# firefly_rp2354A.net
KiCad netlist of a schematic drawn in EasyEDA Pro
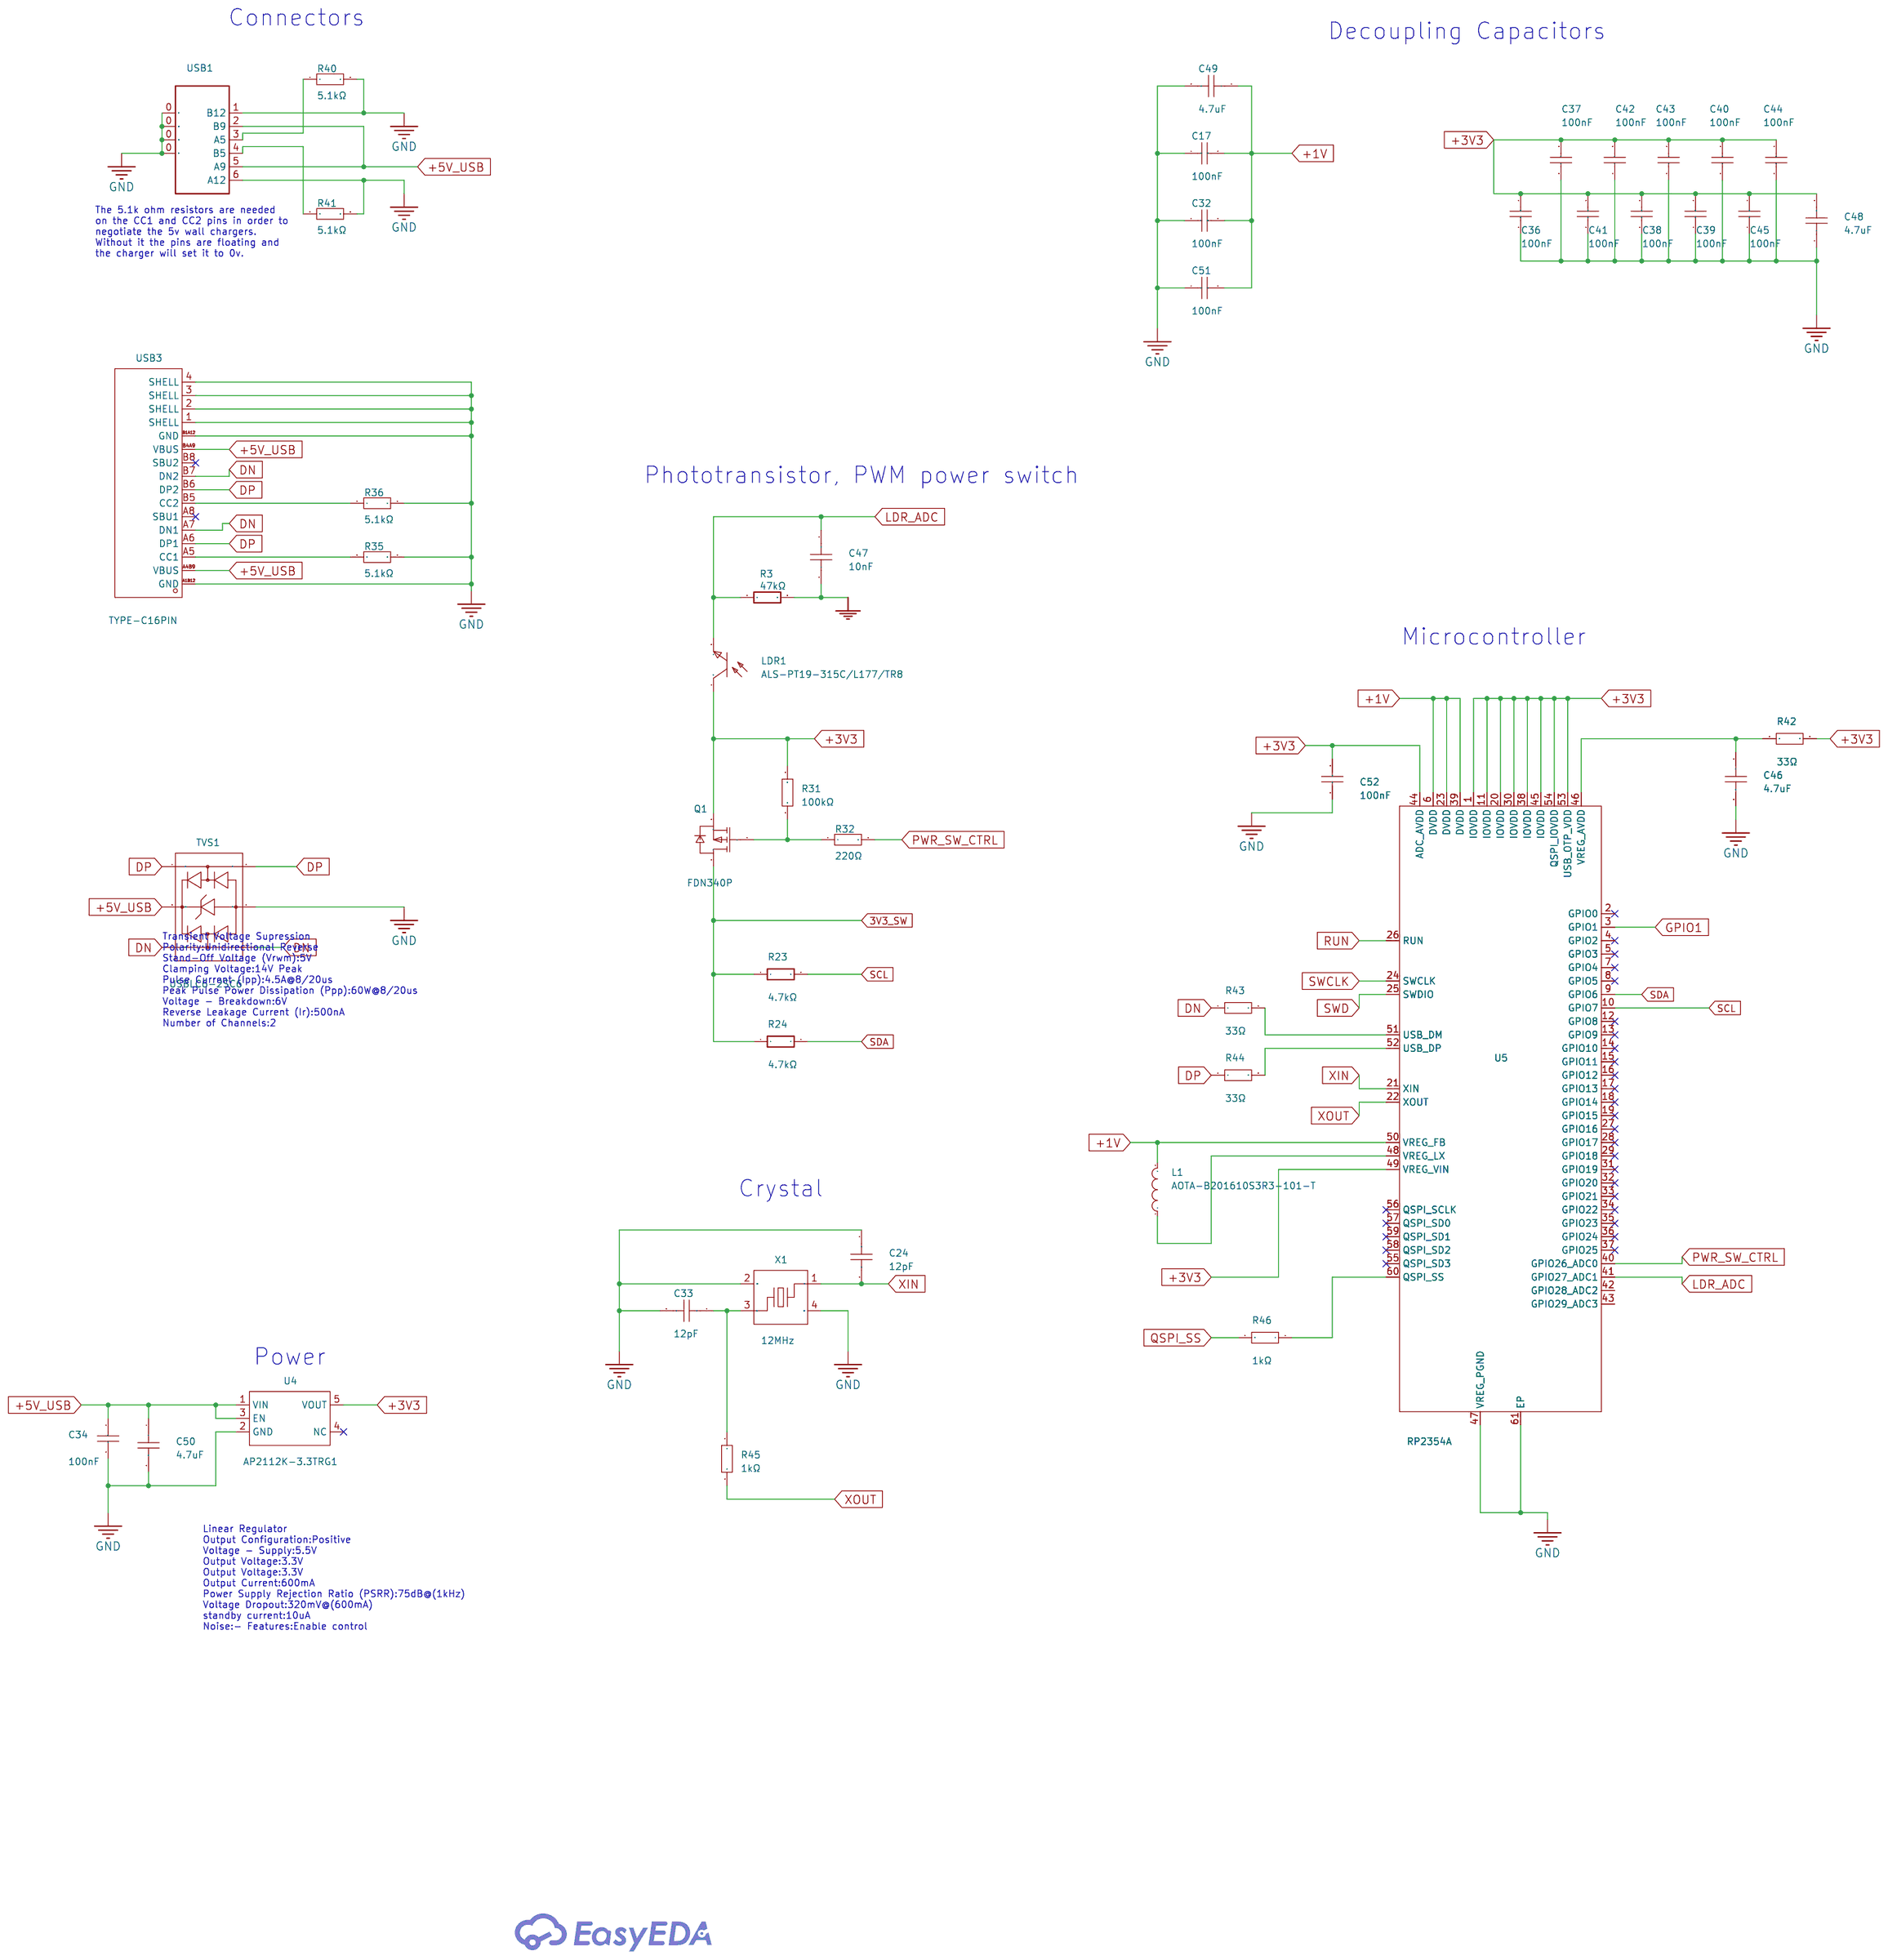
[diagram p0: P1]
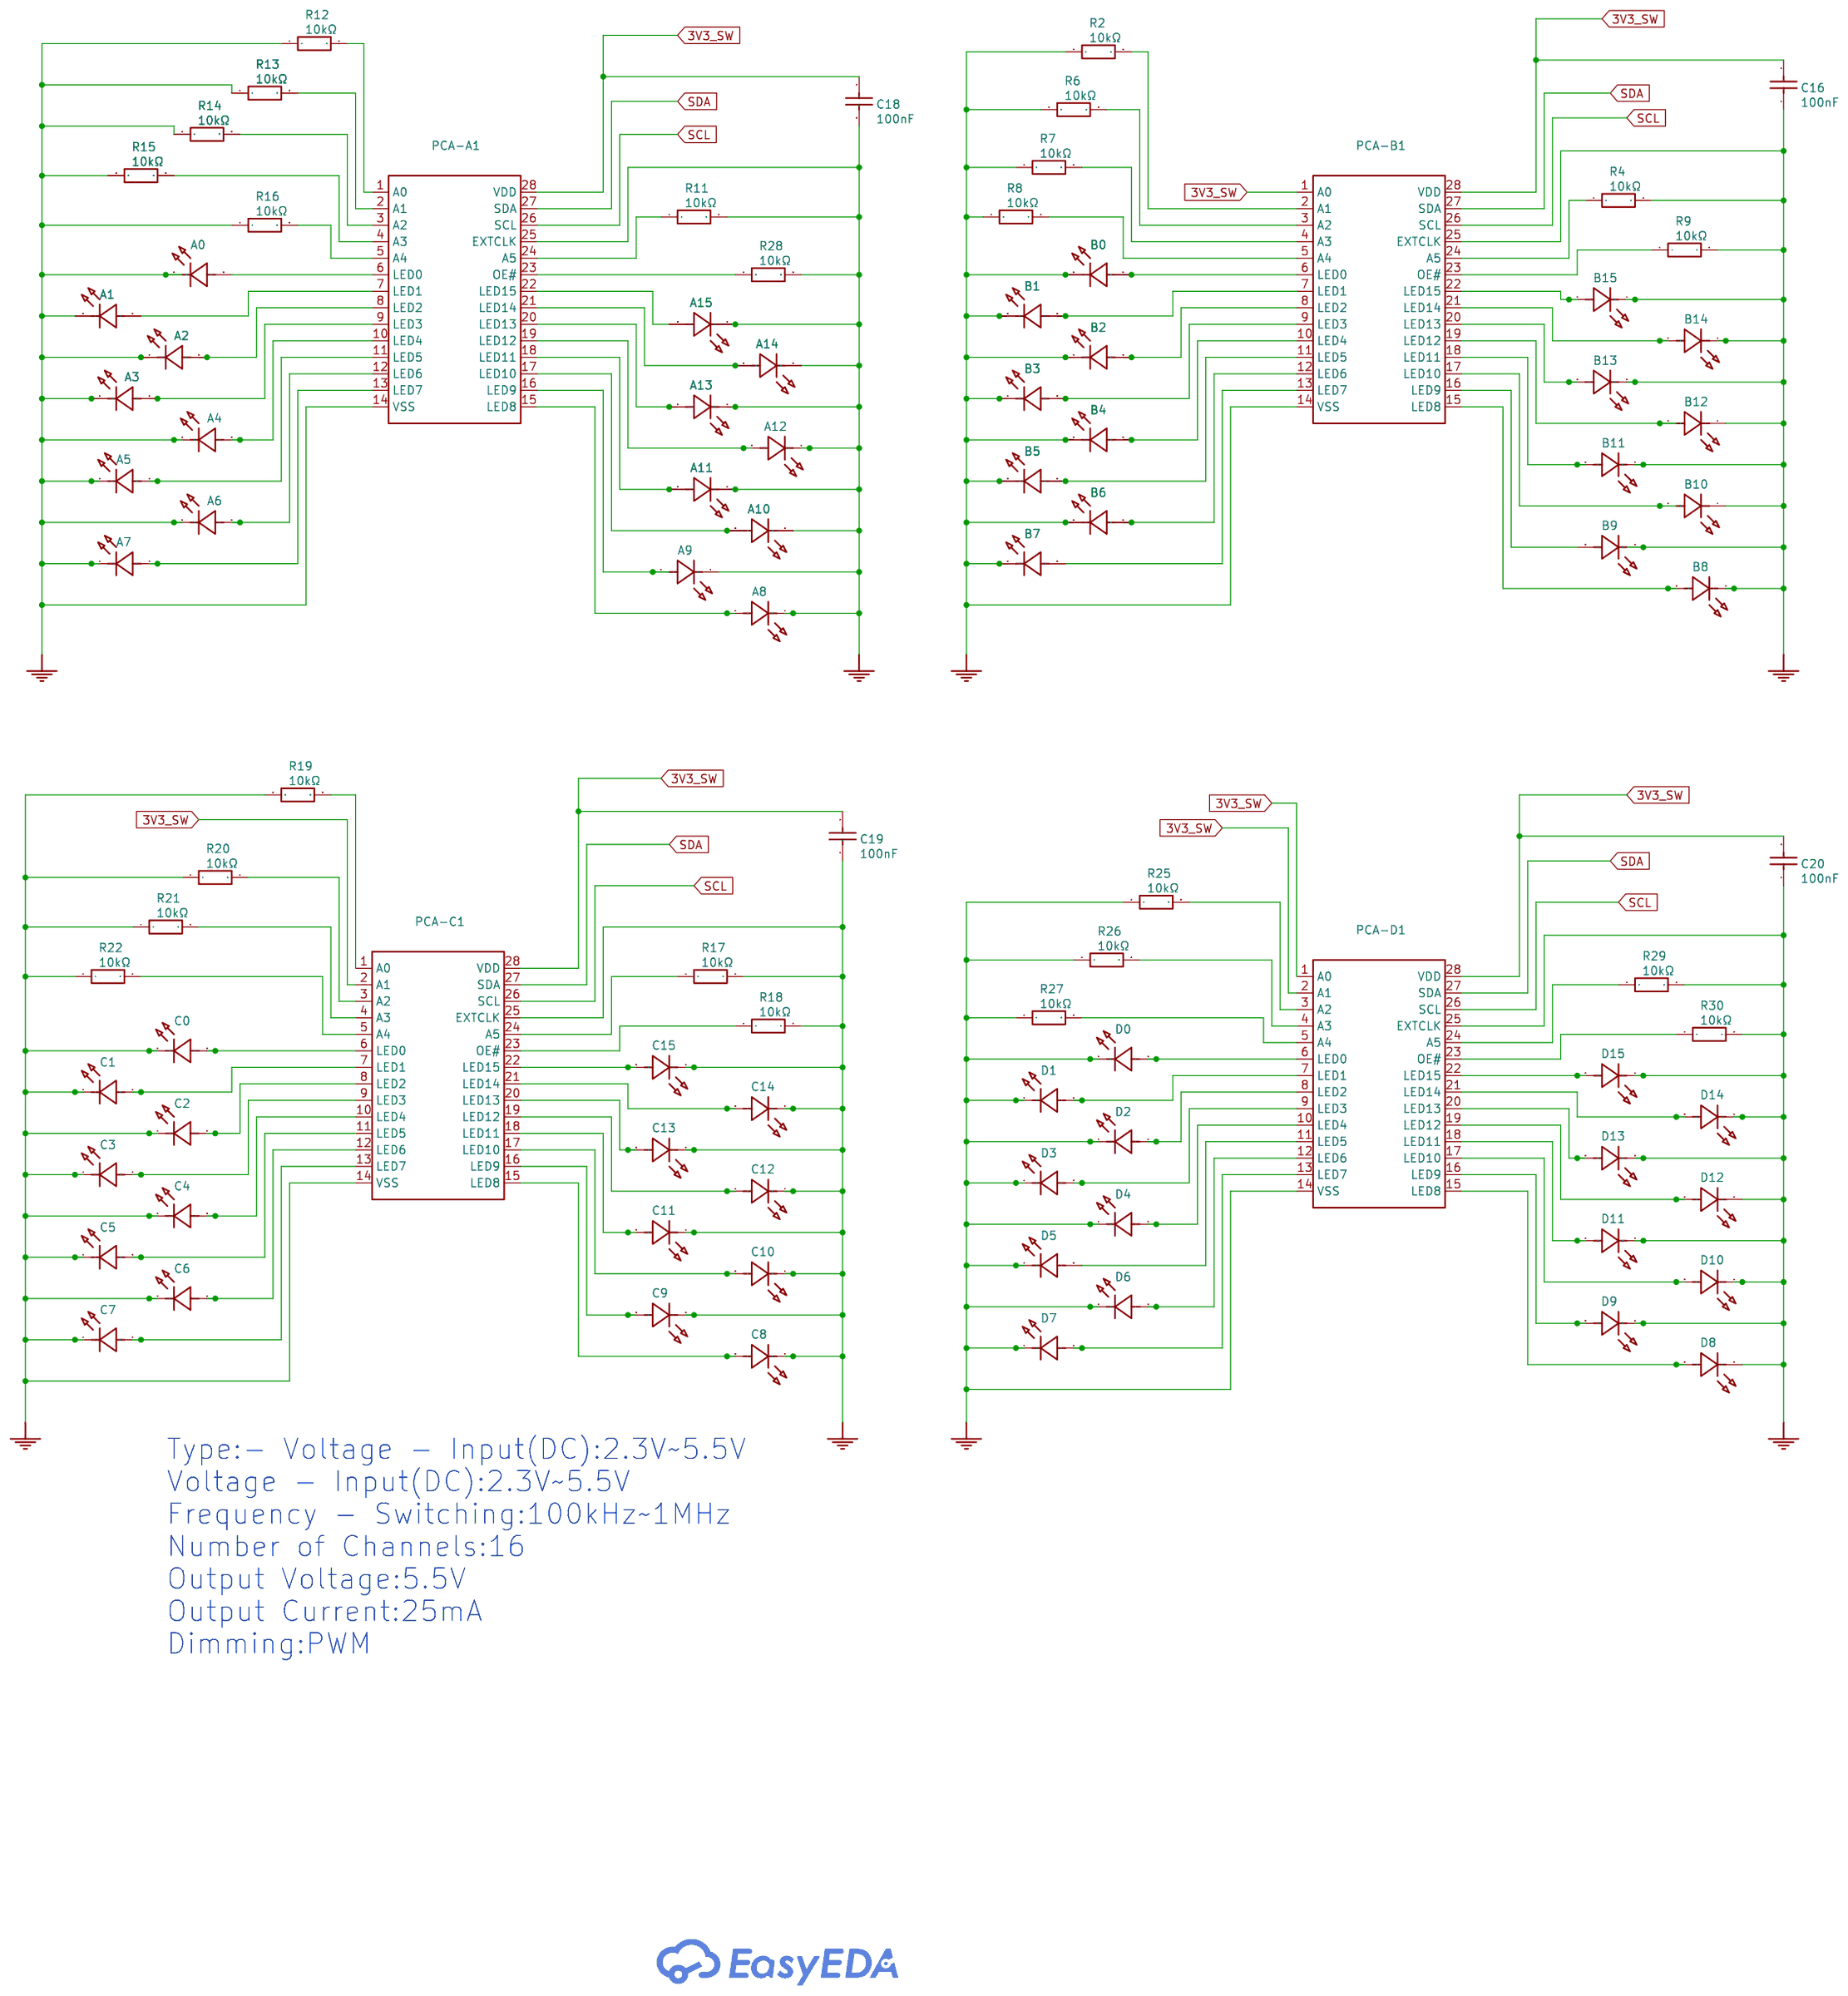
[diagram p1: P2]

(export (version "E")
  (design (tool "Eeschema 10.0.6"))
  (components
    (comp (ref "C17")
      (value "100nF")
      (footprint "easyedapro:C0603")
      (fields
        (field (name "Manufacturer Part") "FCC0402B104K160AT")
        (field (name "Manufacturer") "FOJAN(富捷)")
      )
      (libsource (lib "easyedapro") (part "CL10A105KO8NNNC"))
    )
    (comp (ref "C24")
      (value "12pF")
      (footprint "easyedapro:C0603")
      (fields
        (field (name "Manufacturer Part") "FCC0603N120J500CT")
        (field (name "Manufacturer") "FOJAN(富捷)")
      )
      (libsource (lib "easyedapro") (part "CAP"))
    )
    (comp (ref "C32")
      (value "100nF")
      (footprint "easyedapro:C0603")
      (fields
        (field (name "Manufacturer Part") "FCC0402B104K160AT")
        (field (name "Manufacturer") "FOJAN(富捷)")
      )
      (libsource (lib "easyedapro") (part "CL10A105KO8NNNC"))
    )
    (comp (ref "C33")
      (value "12pF")
      (footprint "easyedapro:C0603")
      (fields
        (field (name "Manufacturer Part") "FCC0603N120J500CT")
        (field (name "Manufacturer") "FOJAN(富捷)")
      )
      (libsource (lib "easyedapro") (part "CAP"))
    )
    (comp (ref "C34")
      (value "100nF")
      (footprint "easyedapro:C0603")
      (fields
        (field (name "Manufacturer Part") "FCC0402B104K160AT")
        (field (name "Manufacturer") "FOJAN(富捷)")
      )
      (libsource (lib "easyedapro") (part "CL10A105KO8NNNC"))
    )
    (comp (ref "C36")
      (value "100nF")
      (footprint "easyedapro:C0603")
      (fields
        (field (name "Manufacturer Part") "FCC0402B104K160AT")
        (field (name "Manufacturer") "FOJAN(富捷)")
      )
      (libsource (lib "easyedapro") (part "CL10A105KO8NNNC"))
    )
    (comp (ref "C37")
      (value "100nF")
      (footprint "easyedapro:C0603")
      (fields
        (field (name "Manufacturer Part") "FCC0402B104K160AT")
        (field (name "Manufacturer") "FOJAN(富捷)")
      )
      (libsource (lib "easyedapro") (part "CL10A105KO8NNNC"))
    )
    (comp (ref "C38")
      (value "100nF")
      (footprint "easyedapro:C0603")
      (fields
        (field (name "Manufacturer Part") "FCC0402B104K160AT")
        (field (name "Manufacturer") "FOJAN(富捷)")
      )
      (libsource (lib "easyedapro") (part "CL10A105KO8NNNC"))
    )
    (comp (ref "C39")
      (value "100nF")
      (footprint "easyedapro:C0603")
      (fields
        (field (name "Manufacturer Part") "FCC0402B104K160AT")
        (field (name "Manufacturer") "FOJAN(富捷)")
      )
      (libsource (lib "easyedapro") (part "CL10A105KO8NNNC"))
    )
    (comp (ref "C40")
      (value "100nF")
      (footprint "easyedapro:C0603")
      (fields
        (field (name "Manufacturer Part") "FCC0402B104K160AT")
        (field (name "Manufacturer") "FOJAN(富捷)")
      )
      (libsource (lib "easyedapro") (part "CL10A105KO8NNNC"))
    )
    (comp (ref "C41")
      (value "100nF")
      (footprint "easyedapro:C0603")
      (fields
        (field (name "Manufacturer Part") "FCC0402B104K160AT")
        (field (name "Manufacturer") "FOJAN(富捷)")
      )
      (libsource (lib "easyedapro") (part "CL10A105KO8NNNC"))
    )
    (comp (ref "C42")
      (value "100nF")
      (footprint "easyedapro:C0603")
      (fields
        (field (name "Manufacturer Part") "FCC0402B104K160AT")
        (field (name "Manufacturer") "FOJAN(富捷)")
      )
      (libsource (lib "easyedapro") (part "CL10A105KO8NNNC"))
    )
    (comp (ref "C43")
      (value "100nF")
      (footprint "easyedapro:C0603")
      (fields
        (field (name "Manufacturer Part") "FCC0402B104K160AT")
        (field (name "Manufacturer") "FOJAN(富捷)")
      )
      (libsource (lib "easyedapro") (part "CL10A105KO8NNNC"))
    )
    (comp (ref "C44")
      (value "100nF")
      (footprint "easyedapro:C0603")
      (fields
        (field (name "Manufacturer Part") "FCC0402B104K160AT")
        (field (name "Manufacturer") "FOJAN(富捷)")
      )
      (libsource (lib "easyedapro") (part "CL10A105KO8NNNC"))
    )
    (comp (ref "C45")
      (value "100nF")
      (footprint "easyedapro:C0603")
      (fields
        (field (name "Manufacturer Part") "FCC0402B104K160AT")
        (field (name "Manufacturer") "FOJAN(富捷)")
      )
      (libsource (lib "easyedapro") (part "CL10A105KO8NNNC"))
    )
    (comp (ref "C46")
      (value "4.7uF")
      (footprint "easyedapro:C0603")
      (description "Capacitance:4.7uF Tolerance:±10% Tolerance:±10% Voltage Rating:10V Temperature Coefficient:X5R")
      (fields
        (field (name "Manufacturer Part") "CL10A475KP8NNNC")
        (field (name "Manufacturer") "SAMSUNG(三星)")
      )
      (libsource (lib "easyedapro") (part "CAP"))
    )
    (comp (ref "C47")
      (value "10nF")
      (footprint "easyedapro:C0603")
      (description "Capacitance:10nF Tolerance:±10% Tolerance:±10% Voltage Rating:50V Temperature Coefficient:X7R")
      (fields (field (name "Manufacturer Part") "FN18X103K500PSG") (field (name "Manufacturer") "PSA(信昌电陶)"))
      (libsource (lib "easyedapro") (part "CAP"))
    )
    (comp (ref "C48")
      (value "4.7uF")
      (footprint "easyedapro:C0603")
      (description "Capacitance:4.7uF Tolerance:±10% Tolerance:±10% Voltage Rating:16V Temperature Coefficient:X5R")
      (fields
        (field (name "Manufacturer Part") "TCC0603X5R475K160CT")
        (field (name "Manufacturer") "CCTC(三环)")
      )
      (libsource (lib "easyedapro") (part "CAP"))
    )
    (comp (ref "C49")
      (value "4.7uF")
      (footprint "easyedapro:C0603")
      (description "Capacitance:4.7uF Tolerance:±10% Tolerance:±10% Voltage Rating:16V Temperature Coefficient:X5R")
      (fields
        (field (name "Manufacturer Part") "TCC0603X5R475K160CT")
        (field (name "Manufacturer") "CCTC(三环)")
      )
      (libsource (lib "easyedapro") (part "CAP"))
    )
    (comp (ref "C50")
      (value "4.7uF")
      (footprint "easyedapro:C0603")
      (description "Capacitance:4.7uF Tolerance:±10% Tolerance:±10% Voltage Rating:16V Temperature Coefficient:X5R")
      (fields
        (field (name "Manufacturer Part") "TCC0603X5R475K160CT")
        (field (name "Manufacturer") "CCTC(三环)")
      )
      (libsource (lib "easyedapro") (part "CAP"))
    )
    (comp (ref "C51")
      (value "100nF")
      (footprint "easyedapro:C0603")
      (fields
        (field (name "Manufacturer Part") "FCC0402B104K160AT")
        (field (name "Manufacturer") "FOJAN(富捷)")
      )
      (libsource (lib "easyedapro") (part "CL10A105KO8NNNC"))
    )
    (comp (ref "C52")
      (value "100nF")
      (footprint "easyedapro:C0603")
      (fields
        (field (name "Manufacturer Part") "FCC0402B104K160AT")
        (field (name "Manufacturer") "FOJAN(富捷)")
      )
      (libsource (lib "easyedapro") (part "CL10A105KO8NNNC"))
    )
    (comp (ref "L1")
      (value "AOTA-B201610S3R3-101-T")
      (footprint "easyedapro:IND-SMD_L2.0-W1.6_AOTA-B201610S3R3-101-T")
      (fields (field (name "Manufacturer") "ABRACON"))
      (libsource (lib "easyedapro") (part "AOTA-B201610S3R3-101-T"))
    )
    (comp (ref "LDR1")
      (value "ALS-PT19-315C/L177/TR8")
      (footprint "easyedapro:SENSORS-SMD_ALS-PT19")
      (fields (field (name "Manufacturer") "EVERLIGHT(亿光)"))
      (libsource (lib "easyedapro") (part "ALS-PT19-315C/L177/TR8"))
    )
    (comp (ref "Q1")
      (value "FDN340P")
      (footprint "easyedapro:SOT-23-3_L3.0-W1.7-P0.95-LS2.9-BR")
      (fields (field (name "Manufacturer") "FUXINSEMI(富芯森美)"))
      (libsource (lib "easyedapro") (part "FDN340P_C22365185"))
    )
    (comp (ref "R3") (value "47kΩ") (libsource (lib "easyedapro") (part "10kΩ")))
    (comp (ref "R23") (value "4.7kΩ") (libsource (lib "easyedapro") (part "4.7kΩ")))
    (comp (ref "R24") (value "4.7kΩ") (libsource (lib "easyedapro") (part "4.7kΩ")))
    (comp (ref "R31")
      (value "100kΩ")
      (footprint "easyedapro:R0603")
      (fields (field (name "Manufacturer Part") "FRC0603J104 TS") (field (name "Manufacturer") "FOJAN(富捷)"))
      (libsource (lib "easyedapro") (part "Res"))
    )
    (comp (ref "R32")
      (value "220Ω")
      (footprint "easyedapro:R0603")
      (fields (field (name "Manufacturer Part") "FRC0603J221 TS") (field (name "Manufacturer") "FOJAN(富捷)"))
      (libsource (lib "easyedapro") (part "Res"))
    )
    (comp (ref "R35")
      (value "5.1kΩ")
      (footprint "easyedapro:R0603")
      (fields (field (name "Manufacturer Part") "FRC0603F5101TS") (field (name "Manufacturer") "FOJAN(富捷)"))
      (libsource (lib "easyedapro") (part "Res"))
    )
    (comp (ref "R36")
      (value "5.1kΩ")
      (footprint "easyedapro:R0603")
      (fields (field (name "Manufacturer Part") "FRC0603F5101TS") (field (name "Manufacturer") "FOJAN(富捷)"))
      (libsource (lib "easyedapro") (part "Res"))
    )
    (comp (ref "R40")
      (value "5.1kΩ")
      (footprint "easyedapro:R0603")
      (fields (field (name "Manufacturer Part") "FRC0603F5101TS") (field (name "Manufacturer") "FOJAN(富捷)"))
      (libsource (lib "easyedapro") (part "Res"))
    )
    (comp (ref "R41")
      (value "5.1kΩ")
      (footprint "easyedapro:R0603")
      (fields (field (name "Manufacturer Part") "FRC0603F5101TS") (field (name "Manufacturer") "FOJAN(富捷)"))
      (libsource (lib "easyedapro") (part "Res"))
    )
    (comp (ref "R42")
      (value "33Ω")
      (footprint "easyedapro:R0603")
      (fields (field (name "Manufacturer Part") "FRC0603F33R0TS") (field (name "Manufacturer") "FOJAN(富捷)"))
      (libsource (lib "easyedapro") (part "Res"))
    )
    (comp (ref "R43")
      (value "33Ω")
      (footprint "easyedapro:R0603")
      (fields (field (name "Manufacturer Part") "FRC0603F33R0TS") (field (name "Manufacturer") "FOJAN(富捷)"))
      (libsource (lib "easyedapro") (part "Res"))
    )
    (comp (ref "R44")
      (value "33Ω")
      (footprint "easyedapro:R0603")
      (fields (field (name "Manufacturer Part") "FRC0603F33R0TS") (field (name "Manufacturer") "FOJAN(富捷)"))
      (libsource (lib "easyedapro") (part "Res"))
    )
    (comp (ref "R45")
      (value "1kΩ")
      (footprint "easyedapro:R0603")
      (fields (field (name "Manufacturer Part") "HRC0603F1001ENTN") (field (name "Manufacturer") "HC(华橙熊猫)"))
      (libsource (lib "easyedapro") (part "Res"))
    )
    (comp (ref "R46")
      (value "1kΩ")
      (footprint "easyedapro:R0603")
      (fields (field (name "Manufacturer Part") "HRC0603F1001ENTN") (field (name "Manufacturer") "HC(华橙熊猫)"))
      (libsource (lib "easyedapro") (part "Res"))
    )
    (comp (ref "TVS1")
      (value "USBLC6-2SC6")
      (footprint "easyedapro:SOT-23-6_L2.9-W1.6-P0.95-LS2.8-BL")
      (fields (field (name "Manufacturer") "GOODWORK(固得沃克)"))
      (libsource (lib "easyedapro") (part "USBLC6-2SC6_C21713975"))
    )
    (comp (ref "U4")
      (value "AP2112K-3.3TRG1")
      (footprint "easyedapro:SOT-23-5_L2.9-W1.6-P0.95-LS2.8-BR")
      (fields (field (name "Manufacturer") "TECH PUBLIC(台舟)"))
      (libsource (lib "easyedapro") (part "AP2112K-3.3TRG1_C23380830"))
    )
    (comp (ref "U5")
      (value "RP2354A")
      (footprint "easyedapro:QFN-60_L7.0-W7.0-P0.40-TL-EP3.4")
      (fields (field (name "Manufacturer") "Raspberry Pi(树莓派)"))
      (libsource (lib "easyedapro") (part "RP2354A"))
    )
    (comp (ref "USB1") (value "USB-312-B-SU") (libsource (lib "easyedapro") (part "USB-312")))
    (comp (ref "USB3")
      (value "TYPE-C16PIN")
      (footprint "easyedapro:USB-C-SMD_TYPE-C16PIN")
      (fields (field (name "Manufacturer") "SHOU HAN(首韩)"))
      (libsource (lib "easyedapro") (part "TYPE-C16PIN"))
    )
    (comp (ref "X1")
      (value "12MHz")
      (footprint "easyedapro:CRYSTAL-SMD_4P-L3.2-W2.5-BL")
      (fields
        (field (name "Manufacturer Part") "TXM12M0004322CBCDO00T")
        (field (name "Manufacturer") "YJX(雅晶鑫)")
      )
      (libsource (lib "easyedapro") (part "3225 12M 18PF 20PPM"))
    )
    (comp (ref "A0")
      (value "XL-2012WWC")
      (footprint "easyedapro:LED0805-RD_WHITE")
      (fields (field (name "Manufacturer") "XINGLIGHT(成兴光)") (field (name "Contributor") "lcsc"))
      (libsource (lib "easyedapro") (part "XL-2012WWC"))
    )
    (comp (ref "A1")
      (value "XL-2012WWC")
      (footprint "easyedapro:LED0805-RD_WHITE")
      (fields (field (name "Manufacturer") "XINGLIGHT(成兴光)") (field (name "Contributor") "lcsc"))
      (libsource (lib "easyedapro") (part "XL-2012WWC"))
    )
    (comp (ref "A2")
      (value "XL-2012WWC")
      (footprint "easyedapro:LED0805-RD_WHITE")
      (fields (field (name "Manufacturer") "XINGLIGHT(成兴光)") (field (name "Contributor") "lcsc"))
      (libsource (lib "easyedapro") (part "XL-2012WWC"))
    )
    (comp (ref "A3")
      (value "XL-2012WWC")
      (footprint "easyedapro:LED0805-RD_WHITE")
      (fields (field (name "Manufacturer") "XINGLIGHT(成兴光)") (field (name "Contributor") "lcsc"))
      (libsource (lib "easyedapro") (part "XL-2012WWC"))
    )
    (comp (ref "A4")
      (value "XL-2012WWC")
      (footprint "easyedapro:LED0805-RD_WHITE")
      (fields (field (name "Manufacturer") "XINGLIGHT(成兴光)") (field (name "Contributor") "lcsc"))
      (libsource (lib "easyedapro") (part "XL-2012WWC"))
    )
    (comp (ref "A5")
      (value "XL-2012WWC")
      (footprint "easyedapro:LED0805-RD_WHITE")
      (fields (field (name "Manufacturer") "XINGLIGHT(成兴光)") (field (name "Contributor") "lcsc"))
      (libsource (lib "easyedapro") (part "XL-2012WWC"))
    )
    (comp (ref "A6")
      (value "XL-2012WWC")
      (footprint "easyedapro:LED0805-RD_WHITE")
      (fields (field (name "Manufacturer") "XINGLIGHT(成兴光)") (field (name "Contributor") "lcsc"))
      (libsource (lib "easyedapro") (part "XL-2012WWC"))
    )
    (comp (ref "A7")
      (value "XL-2012WWC")
      (footprint "easyedapro:LED0805-RD_WHITE")
      (fields (field (name "Manufacturer") "XINGLIGHT(成兴光)") (field (name "Contributor") "lcsc"))
      (libsource (lib "easyedapro") (part "XL-2012WWC"))
    )
    (comp (ref "A8")
      (value "XL-2012WWC")
      (footprint "easyedapro:LED0805-RD_WHITE")
      (fields (field (name "Manufacturer") "XINGLIGHT(成兴光)") (field (name "Contributor") "lcsc"))
      (libsource (lib "easyedapro") (part "XL-2012WWC"))
    )
    (comp (ref "A9")
      (value "XL-2012WWC")
      (footprint "easyedapro:LED0805-RD_WHITE")
      (fields (field (name "Manufacturer") "XINGLIGHT(成兴光)") (field (name "Contributor") "lcsc"))
      (libsource (lib "easyedapro") (part "XL-2012WWC"))
    )
    (comp (ref "A10")
      (value "XL-2012WWC")
      (footprint "easyedapro:LED0805-RD_WHITE")
      (fields (field (name "Manufacturer") "XINGLIGHT(成兴光)") (field (name "Contributor") "lcsc"))
      (libsource (lib "easyedapro") (part "XL-2012WWC"))
    )
    (comp (ref "A11")
      (value "XL-2012WWC")
      (footprint "easyedapro:LED0805-RD_WHITE")
      (fields (field (name "Manufacturer") "XINGLIGHT(成兴光)") (field (name "Contributor") "lcsc"))
      (libsource (lib "easyedapro") (part "XL-2012WWC"))
    )
    (comp (ref "A12")
      (value "XL-2012WWC")
      (footprint "easyedapro:LED0805-RD_WHITE")
      (fields (field (name "Manufacturer") "XINGLIGHT(成兴光)") (field (name "Contributor") "lcsc"))
      (libsource (lib "easyedapro") (part "XL-2012WWC"))
    )
    (comp (ref "A13")
      (value "XL-2012WWC")
      (footprint "easyedapro:LED0805-RD_WHITE")
      (fields (field (name "Manufacturer") "XINGLIGHT(成兴光)") (field (name "Contributor") "lcsc"))
      (libsource (lib "easyedapro") (part "XL-2012WWC"))
    )
    (comp (ref "A14")
      (value "XL-2012WWC")
      (footprint "easyedapro:LED0805-RD_WHITE")
      (fields (field (name "Manufacturer") "XINGLIGHT(成兴光)") (field (name "Contributor") "lcsc"))
      (libsource (lib "easyedapro") (part "XL-2012WWC"))
    )
    (comp (ref "A15")
      (value "XL-2012WWC")
      (footprint "easyedapro:LED0805-RD_WHITE")
      (fields (field (name "Manufacturer") "XINGLIGHT(成兴光)") (field (name "Contributor") "lcsc"))
      (libsource (lib "easyedapro") (part "XL-2012WWC"))
    )
    (comp (ref "B0")
      (value "XL-2012WWC")
      (footprint "easyedapro:LED0805-RD_WHITE")
      (fields (field (name "Manufacturer") "XINGLIGHT(成兴光)") (field (name "Contributor") "lcsc"))
      (libsource (lib "easyedapro") (part "XL-2012WWC"))
    )
    (comp (ref "B1")
      (value "XL-2012WWC")
      (footprint "easyedapro:LED0805-RD_WHITE")
      (fields (field (name "Manufacturer") "XINGLIGHT(成兴光)") (field (name "Contributor") "lcsc"))
      (libsource (lib "easyedapro") (part "XL-2012WWC"))
    )
    (comp (ref "B2")
      (value "XL-2012WWC")
      (footprint "easyedapro:LED0805-RD_WHITE")
      (fields (field (name "Manufacturer") "XINGLIGHT(成兴光)") (field (name "Contributor") "lcsc"))
      (libsource (lib "easyedapro") (part "XL-2012WWC"))
    )
    (comp (ref "B3")
      (value "XL-2012WWC")
      (footprint "easyedapro:LED0805-RD_WHITE")
      (fields (field (name "Manufacturer") "XINGLIGHT(成兴光)") (field (name "Contributor") "lcsc"))
      (libsource (lib "easyedapro") (part "XL-2012WWC"))
    )
    (comp (ref "B4")
      (value "XL-2012WWC")
      (footprint "easyedapro:LED0805-RD_WHITE")
      (fields (field (name "Manufacturer") "XINGLIGHT(成兴光)") (field (name "Contributor") "lcsc"))
      (libsource (lib "easyedapro") (part "XL-2012WWC"))
    )
    (comp (ref "B5")
      (value "XL-2012WWC")
      (footprint "easyedapro:LED0805-RD_WHITE")
      (fields (field (name "Manufacturer") "XINGLIGHT(成兴光)") (field (name "Contributor") "lcsc"))
      (libsource (lib "easyedapro") (part "XL-2012WWC"))
    )
    (comp (ref "B6")
      (value "XL-2012WWC")
      (footprint "easyedapro:LED0805-RD_WHITE")
      (fields (field (name "Manufacturer") "XINGLIGHT(成兴光)") (field (name "Contributor") "lcsc"))
      (libsource (lib "easyedapro") (part "XL-2012WWC"))
    )
    (comp (ref "B7")
      (value "XL-2012WWC")
      (footprint "easyedapro:LED0805-RD_WHITE")
      (fields (field (name "Manufacturer") "XINGLIGHT(成兴光)") (field (name "Contributor") "lcsc"))
      (libsource (lib "easyedapro") (part "XL-2012WWC"))
    )
    (comp (ref "B8")
      (value "XL-2012WWC")
      (footprint "easyedapro:LED0805-RD_WHITE")
      (fields (field (name "Manufacturer") "XINGLIGHT(成兴光)") (field (name "Contributor") "lcsc"))
      (libsource (lib "easyedapro") (part "XL-2012WWC"))
    )
    (comp (ref "B9")
      (value "XL-2012WWC")
      (footprint "easyedapro:LED0805-RD_WHITE")
      (fields (field (name "Manufacturer") "XINGLIGHT(成兴光)") (field (name "Contributor") "lcsc"))
      (libsource (lib "easyedapro") (part "XL-2012WWC"))
    )
    (comp (ref "B10")
      (value "XL-2012WWC")
      (footprint "easyedapro:LED0805-RD_WHITE")
      (fields (field (name "Manufacturer") "XINGLIGHT(成兴光)") (field (name "Contributor") "lcsc"))
      (libsource (lib "easyedapro") (part "XL-2012WWC"))
    )
    (comp (ref "B11")
      (value "XL-2012WWC")
      (footprint "easyedapro:LED0805-RD_WHITE")
      (fields (field (name "Manufacturer") "XINGLIGHT(成兴光)") (field (name "Contributor") "lcsc"))
      (libsource (lib "easyedapro") (part "XL-2012WWC"))
    )
    (comp (ref "B12")
      (value "XL-2012WWC")
      (footprint "easyedapro:LED0805-RD_WHITE")
      (fields (field (name "Manufacturer") "XINGLIGHT(成兴光)") (field (name "Contributor") "lcsc"))
      (libsource (lib "easyedapro") (part "XL-2012WWC"))
    )
    (comp (ref "B13")
      (value "XL-2012WWC")
      (footprint "easyedapro:LED0805-RD_WHITE")
      (fields (field (name "Manufacturer") "XINGLIGHT(成兴光)") (field (name "Contributor") "lcsc"))
      (libsource (lib "easyedapro") (part "XL-2012WWC"))
    )
    (comp (ref "B14")
      (value "XL-2012WWC")
      (footprint "easyedapro:LED0805-RD_WHITE")
      (fields (field (name "Manufacturer") "XINGLIGHT(成兴光)") (field (name "Contributor") "lcsc"))
      (libsource (lib "easyedapro") (part "XL-2012WWC"))
    )
    (comp (ref "B15")
      (value "XL-2012WWC")
      (footprint "easyedapro:LED0805-RD_WHITE")
      (fields (field (name "Manufacturer") "XINGLIGHT(成兴光)") (field (name "Contributor") "lcsc"))
      (libsource (lib "easyedapro") (part "XL-2012WWC"))
    )
    (comp (ref "C0")
      (value "XL-2012WWC")
      (footprint "easyedapro:LED0805-RD_WHITE")
      (fields (field (name "Manufacturer") "XINGLIGHT(成兴光)") (field (name "Contributor") "lcsc"))
      (libsource (lib "easyedapro") (part "XL-2012WWC"))
    )
    (comp (ref "C1")
      (value "XL-2012WWC")
      (footprint "easyedapro:LED0805-RD_WHITE")
      (fields (field (name "Manufacturer") "XINGLIGHT(成兴光)") (field (name "Contributor") "lcsc"))
      (libsource (lib "easyedapro") (part "XL-2012WWC"))
    )
    (comp (ref "C2")
      (value "XL-2012WWC")
      (footprint "easyedapro:LED0805-RD_WHITE")
      (fields (field (name "Manufacturer") "XINGLIGHT(成兴光)") (field (name "Contributor") "lcsc"))
      (libsource (lib "easyedapro") (part "XL-2012WWC"))
    )
    (comp (ref "C3")
      (value "XL-2012WWC")
      (footprint "easyedapro:LED0805-RD_WHITE")
      (fields (field (name "Manufacturer") "XINGLIGHT(成兴光)") (field (name "Contributor") "lcsc"))
      (libsource (lib "easyedapro") (part "XL-2012WWC"))
    )
    (comp (ref "C4")
      (value "XL-2012WWC")
      (footprint "easyedapro:LED0805-RD_WHITE")
      (fields (field (name "Manufacturer") "XINGLIGHT(成兴光)") (field (name "Contributor") "lcsc"))
      (libsource (lib "easyedapro") (part "XL-2012WWC"))
    )
    (comp (ref "C5")
      (value "XL-2012WWC")
      (footprint "easyedapro:LED0805-RD_WHITE")
      (fields (field (name "Manufacturer") "XINGLIGHT(成兴光)") (field (name "Contributor") "lcsc"))
      (libsource (lib "easyedapro") (part "XL-2012WWC"))
    )
    (comp (ref "C6")
      (value "XL-2012WWC")
      (footprint "easyedapro:LED0805-RD_WHITE")
      (fields (field (name "Manufacturer") "XINGLIGHT(成兴光)") (field (name "Contributor") "lcsc"))
      (libsource (lib "easyedapro") (part "XL-2012WWC"))
    )
    (comp (ref "C7")
      (value "XL-2012WWC")
      (footprint "easyedapro:LED0805-RD_WHITE")
      (fields (field (name "Manufacturer") "XINGLIGHT(成兴光)") (field (name "Contributor") "lcsc"))
      (libsource (lib "easyedapro") (part "XL-2012WWC"))
    )
    (comp (ref "C8")
      (value "XL-2012WWC")
      (footprint "easyedapro:LED0805-RD_WHITE")
      (fields (field (name "Manufacturer") "XINGLIGHT(成兴光)") (field (name "Contributor") "lcsc"))
      (libsource (lib "easyedapro") (part "XL-2012WWC"))
    )
    (comp (ref "C9")
      (value "XL-2012WWC")
      (footprint "easyedapro:LED0805-RD_WHITE")
      (fields (field (name "Manufacturer") "XINGLIGHT(成兴光)") (field (name "Contributor") "lcsc"))
      (libsource (lib "easyedapro") (part "XL-2012WWC"))
    )
    (comp (ref "C10")
      (value "XL-2012WWC")
      (footprint "easyedapro:LED0805-RD_WHITE")
      (fields (field (name "Manufacturer") "XINGLIGHT(成兴光)") (field (name "Contributor") "lcsc"))
      (libsource (lib "easyedapro") (part "XL-2012WWC"))
    )
    (comp (ref "C11")
      (value "XL-2012WWC")
      (footprint "easyedapro:LED0805-RD_WHITE")
      (fields (field (name "Manufacturer") "XINGLIGHT(成兴光)") (field (name "Contributor") "lcsc"))
      (libsource (lib "easyedapro") (part "XL-2012WWC"))
    )
    (comp (ref "C12")
      (value "XL-2012WWC")
      (footprint "easyedapro:LED0805-RD_WHITE")
      (fields (field (name "Manufacturer") "XINGLIGHT(成兴光)") (field (name "Contributor") "lcsc"))
      (libsource (lib "easyedapro") (part "XL-2012WWC"))
    )
    (comp (ref "C13")
      (value "XL-2012WWC")
      (footprint "easyedapro:LED0805-RD_WHITE")
      (fields (field (name "Manufacturer") "XINGLIGHT(成兴光)") (field (name "Contributor") "lcsc"))
      (libsource (lib "easyedapro") (part "XL-2012WWC"))
    )
    (comp (ref "C14")
      (value "XL-2012WWC")
      (footprint "easyedapro:LED0805-RD_WHITE")
      (fields (field (name "Manufacturer") "XINGLIGHT(成兴光)") (field (name "Contributor") "lcsc"))
      (libsource (lib "easyedapro") (part "XL-2012WWC"))
    )
    (comp (ref "C15")
      (value "XL-2012WWC")
      (footprint "easyedapro:LED0805-RD_WHITE")
      (fields (field (name "Manufacturer") "XINGLIGHT(成兴光)") (field (name "Contributor") "lcsc"))
      (libsource (lib "easyedapro") (part "XL-2012WWC"))
    )
    (comp (ref "C16")
      (value "100nF")
      (fields
        (field (name "Manufacturer Part") "FCC0402B104K160AT")
        (field (name "Manufacturer") "FOJAN(富捷)")
      )
      (libsource (lib "easyedapro") (part "100nF"))
    )
    (comp (ref "C18")
      (value "100nF")
      (fields
        (field (name "Manufacturer Part") "FCC0402B104K160AT")
        (field (name "Manufacturer") "FOJAN(富捷)")
      )
      (libsource (lib "easyedapro") (part "100nF"))
    )
    (comp (ref "C19")
      (value "100nF")
      (fields
        (field (name "Manufacturer Part") "FCC0402B104K160AT")
        (field (name "Manufacturer") "FOJAN(富捷)")
      )
      (libsource (lib "easyedapro") (part "100nF"))
    )
    (comp (ref "C20")
      (value "100nF")
      (fields
        (field (name "Manufacturer Part") "FCC0402B104K160AT")
        (field (name "Manufacturer") "FOJAN(富捷)")
      )
      (libsource (lib "easyedapro") (part "100nF"))
    )
    (comp (ref "D0")
      (value "XL-2012WWC")
      (footprint "easyedapro:LED0805-RD_WHITE")
      (fields (field (name "Manufacturer") "XINGLIGHT(成兴光)") (field (name "Contributor") "lcsc"))
      (libsource (lib "easyedapro") (part "XL-2012WWC"))
    )
    (comp (ref "D1")
      (value "XL-2012WWC")
      (footprint "easyedapro:LED0805-RD_WHITE")
      (fields (field (name "Manufacturer") "XINGLIGHT(成兴光)") (field (name "Contributor") "lcsc"))
      (libsource (lib "easyedapro") (part "XL-2012WWC"))
    )
    (comp (ref "D2")
      (value "XL-2012WWC")
      (footprint "easyedapro:LED0805-RD_WHITE")
      (fields (field (name "Manufacturer") "XINGLIGHT(成兴光)") (field (name "Contributor") "lcsc"))
      (libsource (lib "easyedapro") (part "XL-2012WWC"))
    )
    (comp (ref "D3")
      (value "XL-2012WWC")
      (footprint "easyedapro:LED0805-RD_WHITE")
      (fields (field (name "Manufacturer") "XINGLIGHT(成兴光)") (field (name "Contributor") "lcsc"))
      (libsource (lib "easyedapro") (part "XL-2012WWC"))
    )
    (comp (ref "D4")
      (value "XL-2012WWC")
      (footprint "easyedapro:LED0805-RD_WHITE")
      (fields (field (name "Manufacturer") "XINGLIGHT(成兴光)") (field (name "Contributor") "lcsc"))
      (libsource (lib "easyedapro") (part "XL-2012WWC"))
    )
    (comp (ref "D5")
      (value "XL-2012WWC")
      (footprint "easyedapro:LED0805-RD_WHITE")
      (fields (field (name "Manufacturer") "XINGLIGHT(成兴光)") (field (name "Contributor") "lcsc"))
      (libsource (lib "easyedapro") (part "XL-2012WWC"))
    )
    (comp (ref "D6")
      (value "XL-2012WWC")
      (footprint "easyedapro:LED0805-RD_WHITE")
      (fields (field (name "Manufacturer") "XINGLIGHT(成兴光)") (field (name "Contributor") "lcsc"))
      (libsource (lib "easyedapro") (part "XL-2012WWC"))
    )
    (comp (ref "D7")
      (value "XL-2012WWC")
      (footprint "easyedapro:LED0805-RD_WHITE")
      (fields (field (name "Manufacturer") "XINGLIGHT(成兴光)") (field (name "Contributor") "lcsc"))
      (libsource (lib "easyedapro") (part "XL-2012WWC"))
    )
    (comp (ref "D8")
      (value "XL-2012WWC")
      (footprint "easyedapro:LED0805-RD_WHITE")
      (fields (field (name "Manufacturer") "XINGLIGHT(成兴光)") (field (name "Contributor") "lcsc"))
      (libsource (lib "easyedapro") (part "XL-2012WWC"))
    )
    (comp (ref "D9")
      (value "XL-2012WWC")
      (footprint "easyedapro:LED0805-RD_WHITE")
      (fields (field (name "Manufacturer") "XINGLIGHT(成兴光)") (field (name "Contributor") "lcsc"))
      (libsource (lib "easyedapro") (part "XL-2012WWC"))
    )
    (comp (ref "D10")
      (value "XL-2012WWC")
      (footprint "easyedapro:LED0805-RD_WHITE")
      (fields (field (name "Manufacturer") "XINGLIGHT(成兴光)") (field (name "Contributor") "lcsc"))
      (libsource (lib "easyedapro") (part "XL-2012WWC"))
    )
    (comp (ref "D11")
      (value "XL-2012WWC")
      (footprint "easyedapro:LED0805-RD_WHITE")
      (fields (field (name "Manufacturer") "XINGLIGHT(成兴光)") (field (name "Contributor") "lcsc"))
      (libsource (lib "easyedapro") (part "XL-2012WWC"))
    )
    (comp (ref "D12")
      (value "XL-2012WWC")
      (footprint "easyedapro:LED0805-RD_WHITE")
      (fields (field (name "Manufacturer") "XINGLIGHT(成兴光)") (field (name "Contributor") "lcsc"))
      (libsource (lib "easyedapro") (part "XL-2012WWC"))
    )
    (comp (ref "D13")
      (value "XL-2012WWC")
      (footprint "easyedapro:LED0805-RD_WHITE")
      (fields (field (name "Manufacturer") "XINGLIGHT(成兴光)") (field (name "Contributor") "lcsc"))
      (libsource (lib "easyedapro") (part "XL-2012WWC"))
    )
    (comp (ref "D14")
      (value "XL-2012WWC")
      (footprint "easyedapro:LED0805-RD_WHITE")
      (fields (field (name "Manufacturer") "XINGLIGHT(成兴光)") (field (name "Contributor") "lcsc"))
      (libsource (lib "easyedapro") (part "XL-2012WWC"))
    )
    (comp (ref "D15")
      (value "XL-2012WWC")
      (footprint "easyedapro:LED0805-RD_WHITE")
      (fields (field (name "Manufacturer") "XINGLIGHT(成兴光)") (field (name "Contributor") "lcsc"))
      (libsource (lib "easyedapro") (part "XL-2012WWC"))
    )
    (comp (ref "PCA-A1") (value "PCA9685PW,118") (libsource (lib "easyedapro") (part "PCA9685PW")))
    (comp (ref "PCA-B1") (value "PCA9685PW,118") (libsource (lib "easyedapro") (part "PCA9685PW")))
    (comp (ref "PCA-C1") (value "PCA9685PW,118") (libsource (lib "easyedapro") (part "PCA9685PW")))
    (comp (ref "PCA-D1") (value "PCA9685PW,118") (libsource (lib "easyedapro") (part "PCA9685PW")))
    (comp (ref "R2") (value "10kΩ") (libsource (lib "easyedapro") (part "10kΩ")))
    (comp (ref "R4") (value "10kΩ") (libsource (lib "easyedapro") (part "10kΩ")))
    (comp (ref "R6") (value "10kΩ") (libsource (lib "easyedapro") (part "10kΩ")))
    (comp (ref "R7") (value "10kΩ") (libsource (lib "easyedapro") (part "10kΩ")))
    (comp (ref "R8") (value "10kΩ") (libsource (lib "easyedapro") (part "10kΩ")))
    (comp (ref "R9") (value "10kΩ") (libsource (lib "easyedapro") (part "10kΩ")))
    (comp (ref "R11") (value "10kΩ") (libsource (lib "easyedapro") (part "10kΩ")))
    (comp (ref "R12") (value "10kΩ") (libsource (lib "easyedapro") (part "10kΩ")))
    (comp (ref "R13") (value "10kΩ") (libsource (lib "easyedapro") (part "10kΩ")))
    (comp (ref "R14") (value "10kΩ") (libsource (lib "easyedapro") (part "10kΩ")))
    (comp (ref "R15") (value "10kΩ") (libsource (lib "easyedapro") (part "10kΩ")))
    (comp (ref "R16") (value "10kΩ") (libsource (lib "easyedapro") (part "10kΩ")))
    (comp (ref "R17") (value "10kΩ") (libsource (lib "easyedapro") (part "10kΩ")))
    (comp (ref "R18") (value "10kΩ") (libsource (lib "easyedapro") (part "10kΩ")))
    (comp (ref "R19") (value "10kΩ") (libsource (lib "easyedapro") (part "10kΩ")))
    (comp (ref "R20") (value "10kΩ") (libsource (lib "easyedapro") (part "10kΩ")))
    (comp (ref "R21") (value "10kΩ") (libsource (lib "easyedapro") (part "10kΩ")))
    (comp (ref "R22") (value "10kΩ") (libsource (lib "easyedapro") (part "10kΩ")))
    (comp (ref "R25") (value "10kΩ") (libsource (lib "easyedapro") (part "10kΩ")))
    (comp (ref "R26") (value "10kΩ") (libsource (lib "easyedapro") (part "10kΩ")))
    (comp (ref "R27") (value "10kΩ") (libsource (lib "easyedapro") (part "10kΩ")))
    (comp (ref "R28") (value "10kΩ") (libsource (lib "easyedapro") (part "10kΩ")))
    (comp (ref "R29") (value "10kΩ") (libsource (lib "easyedapro") (part "10kΩ")))
    (comp (ref "R30") (value "10kΩ") (libsource (lib "easyedapro") (part "10kΩ")))
  )
  (nets
    (net (code "1") (name "+1V") (class "Default")
      (node (ref "C17") (pin "2") (pinfunction "2_2") (pintype "input"))
      (node (ref "C32") (pin "2") (pinfunction "2_2") (pintype "input"))
      (node (ref "C49") (pin "1") (pinfunction "1_1") (pintype "input"))
      (node (ref "C51") (pin "2") (pinfunction "2_2") (pintype "input"))
      (node (ref "L1") (pin "2") (pinfunction "2_2") (pintype "unspecified"))
      (node (ref "U5") (pin "23") (pinfunction "DVDD_23") (pintype "unspecified"))
      (node (ref "U5") (pin "39") (pinfunction "DVDD_39") (pintype "unspecified"))
      (node (ref "U5") (pin "50") (pinfunction "VREG_FB_50") (pintype "unspecified"))
      (node (ref "U5") (pin "6") (pinfunction "DVDD_6") (pintype "unspecified"))
    )
    (net (code "2") (name "+3V3") (class "Default")
      (node (ref "C36") (pin "2") (pinfunction "2_2") (pintype "input"))
      (node (ref "C37") (pin "2") (pinfunction "2_2") (pintype "input"))
      (node (ref "C38") (pin "2") (pinfunction "2_2") (pintype "input"))
      (node (ref "C39") (pin "2") (pinfunction "2_2") (pintype "input"))
      (node (ref "C40") (pin "2") (pinfunction "2_2") (pintype "input"))
      (node (ref "C41") (pin "2") (pinfunction "2_2") (pintype "input"))
      (node (ref "C42") (pin "2") (pinfunction "2_2") (pintype "input"))
      (node (ref "C43") (pin "2") (pinfunction "2_2") (pintype "input"))
      (node (ref "C44") (pin "2") (pinfunction "2_2") (pintype "input"))
      (node (ref "C45") (pin "2") (pinfunction "2_2") (pintype "input"))
      (node (ref "C48") (pin "2") (pinfunction "2_2") (pintype "input"))
      (node (ref "C52") (pin "1") (pinfunction "1_1") (pintype "input"))
      (node (ref "LDR1") (pin "1") (pinfunction "C_1") (pintype "input"))
      (node (ref "Q1") (pin "2") (pinfunction "S_2") (pintype "unspecified"))
      (node (ref "R31") (pin "2") (pinfunction "2_2") (pintype "input"))
      (node (ref "R42") (pin "2") (pinfunction "2_2") (pintype "input"))
      (node (ref "U4") (pin "5") (pinfunction "VOUT_5") (pintype "unspecified"))
      (node (ref "U5") (pin "1") (pinfunction "IOVDD_1") (pintype "unspecified"))
      (node (ref "U5") (pin "11") (pinfunction "IOVDD_11") (pintype "unspecified"))
      (node (ref "U5") (pin "20") (pinfunction "IOVDD_20") (pintype "unspecified"))
      (node (ref "U5") (pin "30") (pinfunction "IOVDD_30") (pintype "unspecified"))
      (node (ref "U5") (pin "38") (pinfunction "IOVDD_38") (pintype "unspecified"))
      (node (ref "U5") (pin "44") (pinfunction "ADC_AVDD_44") (pintype "unspecified"))
      (node (ref "U5") (pin "45") (pinfunction "IOVDD_45") (pintype "unspecified"))
      (node (ref "U5") (pin "49") (pinfunction "VREG_VIN_49") (pintype "unspecified"))
      (node (ref "U5") (pin "53") (pinfunction "USB_OTP_VDD_53") (pintype "unspecified"))
      (node (ref "U5") (pin "54") (pinfunction "QSPI_IOVDD_54") (pintype "unspecified"))
    )
    (net (code "3") (name "+5V_USB") (class "Default")
      (node (ref "C34") (pin "2") (pinfunction "2_2") (pintype "input"))
      (node (ref "C50") (pin "1") (pinfunction "1_1") (pintype "input"))
      (node (ref "TVS1") (pin "5") (pinfunction "VBUS_5") (pintype "unspecified"))
      (node (ref "U4") (pin "1") (pinfunction "VIN_1") (pintype "unspecified"))
      (node (ref "U4") (pin "3") (pinfunction "EN_3") (pintype "unspecified"))
      (node (ref "USB1") (pin "2") (pinfunction "B9_2") (pintype "unspecified"))
      (node (ref "USB1") (pin "5") (pinfunction "A9_5") (pintype "unspecified"))
      (node (ref "USB3") (pin "A4B9") (pinfunction "VBUS_A4B9") (pintype "unspecified"))
      (node (ref "USB3") (pin "B4A9") (pinfunction "VBUS_B4A9") (pintype "unspecified"))
    )
    (net (code "4") (name "3V3_SW") (class "Default")
      (node (ref "C16") (pin "2") (pinfunction "2_2") (pintype "input"))
      (node (ref "C18") (pin "2") (pinfunction "2_2") (pintype "input"))
      (node (ref "C19") (pin "2") (pinfunction "2_2") (pintype "input"))
      (node (ref "C20") (pin "2") (pinfunction "2_2") (pintype "input"))
      (node (ref "PCA-A1") (pin "28") (pinfunction "VDD_28") (pintype "unspecified"))
      (node (ref "PCA-B1") (pin "1") (pinfunction "A0_1") (pintype "unspecified"))
      (node (ref "PCA-B1") (pin "28") (pinfunction "VDD_28") (pintype "unspecified"))
      (node (ref "PCA-C1") (pin "2") (pinfunction "A1_2") (pintype "unspecified"))
      (node (ref "PCA-C1") (pin "28") (pinfunction "VDD_28") (pintype "unspecified"))
      (node (ref "PCA-D1") (pin "1") (pinfunction "A0_1") (pintype "unspecified"))
      (node (ref "PCA-D1") (pin "2") (pinfunction "A1_2") (pintype "unspecified"))
      (node (ref "PCA-D1") (pin "28") (pinfunction "VDD_28") (pintype "unspecified"))
      (node (ref "Q1") (pin "3") (pinfunction "D_3") (pintype "unspecified"))
      (node (ref "R23") (pin "1") (pinfunction "1_1") (pintype "input"))
      (node (ref "R24") (pin "1") (pinfunction "1_1") (pintype "input"))
    )
    (net (code "5") (name "DN") (class "Default")
      (node (ref "R43") (pin "1") (pinfunction "1_1") (pintype "input"))
      (node (ref "TVS1") (pin "1") (pinfunction "I/O1_1") (pintype "unspecified"))
      (node (ref "TVS1") (pin "6") (pinfunction "I/O1_6") (pintype "unspecified"))
      (node (ref "USB3") (pin "A7") (pinfunction "DN1_A7") (pintype "unspecified"))
      (node (ref "USB3") (pin "B7") (pinfunction "DN2_B7") (pintype "unspecified"))
    )
    (net (code "6") (name "DP") (class "Default")
      (node (ref "R44") (pin "1") (pinfunction "1_1") (pintype "input"))
      (node (ref "TVS1") (pin "3") (pinfunction "I/O2_3") (pintype "unspecified"))
      (node (ref "TVS1") (pin "4") (pinfunction "I/O2_4") (pintype "unspecified"))
      (node (ref "USB3") (pin "A6") (pinfunction "DP1_A6") (pintype "unspecified"))
      (node (ref "USB3") (pin "B6") (pinfunction "DP2_B6") (pintype "unspecified"))
    )
    (net (code "7") (name "GND") (class "Default")
      (node (ref "A0") (pin "1") (pinfunction "K_1") (pintype "unspecified"))
      (node (ref "A1") (pin "1") (pinfunction "K_1") (pintype "unspecified"))
      (node (ref "A10") (pin "1") (pinfunction "K_1") (pintype "unspecified"))
      (node (ref "A11") (pin "1") (pinfunction "K_1") (pintype "unspecified"))
      (node (ref "A12") (pin "1") (pinfunction "K_1") (pintype "unspecified"))
      (node (ref "A13") (pin "1") (pinfunction "K_1") (pintype "unspecified"))
      (node (ref "A14") (pin "1") (pinfunction "K_1") (pintype "unspecified"))
      (node (ref "A15") (pin "1") (pinfunction "K_1") (pintype "unspecified"))
      (node (ref "A2") (pin "1") (pinfunction "K_1") (pintype "unspecified"))
      (node (ref "A3") (pin "1") (pinfunction "K_1") (pintype "unspecified"))
      (node (ref "A4") (pin "1") (pinfunction "K_1") (pintype "unspecified"))
      (node (ref "A5") (pin "1") (pinfunction "K_1") (pintype "unspecified"))
      (node (ref "A6") (pin "1") (pinfunction "K_1") (pintype "unspecified"))
      (node (ref "A7") (pin "1") (pinfunction "K_1") (pintype "unspecified"))
      (node (ref "A8") (pin "1") (pinfunction "K_1") (pintype "unspecified"))
      (node (ref "A9") (pin "1") (pinfunction "K_1") (pintype "unspecified"))
      (node (ref "B0") (pin "1") (pinfunction "K_1") (pintype "unspecified"))
      (node (ref "B1") (pin "1") (pinfunction "K_1") (pintype "unspecified"))
      (node (ref "B10") (pin "1") (pinfunction "K_1") (pintype "unspecified"))
      (node (ref "B11") (pin "1") (pinfunction "K_1") (pintype "unspecified"))
      (node (ref "B12") (pin "1") (pinfunction "K_1") (pintype "unspecified"))
      (node (ref "B13") (pin "1") (pinfunction "K_1") (pintype "unspecified"))
      (node (ref "B14") (pin "1") (pinfunction "K_1") (pintype "unspecified"))
      (node (ref "B15") (pin "1") (pinfunction "K_1") (pintype "unspecified"))
      (node (ref "B2") (pin "1") (pinfunction "K_1") (pintype "unspecified"))
      (node (ref "B3") (pin "1") (pinfunction "K_1") (pintype "unspecified"))
      (node (ref "B4") (pin "1") (pinfunction "K_1") (pintype "unspecified"))
      (node (ref "B5") (pin "1") (pinfunction "K_1") (pintype "unspecified"))
      (node (ref "B6") (pin "1") (pinfunction "K_1") (pintype "unspecified"))
      (node (ref "B7") (pin "1") (pinfunction "K_1") (pintype "unspecified"))
      (node (ref "B8") (pin "1") (pinfunction "K_1") (pintype "unspecified"))
      (node (ref "B9") (pin "1") (pinfunction "K_1") (pintype "unspecified"))
      (node (ref "C0") (pin "1") (pinfunction "K_1") (pintype "unspecified"))
      (node (ref "C1") (pin "1") (pinfunction "K_1") (pintype "unspecified"))
      (node (ref "C10") (pin "1") (pinfunction "K_1") (pintype "unspecified"))
      (node (ref "C11") (pin "1") (pinfunction "K_1") (pintype "unspecified"))
      (node (ref "C12") (pin "1") (pinfunction "K_1") (pintype "unspecified"))
      (node (ref "C13") (pin "1") (pinfunction "K_1") (pintype "unspecified"))
      (node (ref "C14") (pin "1") (pinfunction "K_1") (pintype "unspecified"))
      (node (ref "C15") (pin "1") (pinfunction "K_1") (pintype "unspecified"))
      (node (ref "C16") (pin "1") (pinfunction "1_1") (pintype "input"))
      (node (ref "C17") (pin "1") (pinfunction "1_1") (pintype "input"))
      (node (ref "C18") (pin "1") (pinfunction "1_1") (pintype "input"))
      (node (ref "C19") (pin "1") (pinfunction "1_1") (pintype "input"))
      (node (ref "C2") (pin "1") (pinfunction "K_1") (pintype "unspecified"))
      (node (ref "C20") (pin "1") (pinfunction "1_1") (pintype "input"))
      (node (ref "C24") (pin "1") (pinfunction "1_1") (pintype "input"))
      (node (ref "C3") (pin "1") (pinfunction "K_1") (pintype "unspecified"))
      (node (ref "C32") (pin "1") (pinfunction "1_1") (pintype "input"))
      (node (ref "C33") (pin "2") (pinfunction "2_2") (pintype "input"))
      (node (ref "C34") (pin "1") (pinfunction "1_1") (pintype "input"))
      (node (ref "C36") (pin "1") (pinfunction "1_1") (pintype "input"))
      (node (ref "C37") (pin "1") (pinfunction "1_1") (pintype "input"))
      (node (ref "C38") (pin "1") (pinfunction "1_1") (pintype "input"))
      (node (ref "C39") (pin "1") (pinfunction "1_1") (pintype "input"))
      (node (ref "C4") (pin "1") (pinfunction "K_1") (pintype "unspecified"))
      (node (ref "C40") (pin "1") (pinfunction "1_1") (pintype "input"))
      (node (ref "C41") (pin "1") (pinfunction "1_1") (pintype "input"))
      (node (ref "C42") (pin "1") (pinfunction "1_1") (pintype "input"))
      (node (ref "C43") (pin "1") (pinfunction "1_1") (pintype "input"))
      (node (ref "C44") (pin "1") (pinfunction "1_1") (pintype "input"))
      (node (ref "C45") (pin "1") (pinfunction "1_1") (pintype "input"))
      (node (ref "C46") (pin "2") (pinfunction "2_2") (pintype "input"))
      (node (ref "C47") (pin "2") (pinfunction "2_2") (pintype "input"))
      (node (ref "C48") (pin "1") (pinfunction "1_1") (pintype "input"))
      (node (ref "C49") (pin "2") (pinfunction "2_2") (pintype "input"))
      (node (ref "C5") (pin "1") (pinfunction "K_1") (pintype "unspecified"))
      (node (ref "C50") (pin "2") (pinfunction "2_2") (pintype "input"))
      (node (ref "C51") (pin "1") (pinfunction "1_1") (pintype "input"))
      (node (ref "C52") (pin "2") (pinfunction "2_2") (pintype "input"))
      (node (ref "C6") (pin "1") (pinfunction "K_1") (pintype "unspecified"))
      (node (ref "C7") (pin "1") (pinfunction "K_1") (pintype "unspecified"))
      (node (ref "C8") (pin "1") (pinfunction "K_1") (pintype "unspecified"))
      (node (ref "C9") (pin "1") (pinfunction "K_1") (pintype "unspecified"))
      (node (ref "D0") (pin "1") (pinfunction "K_1") (pintype "unspecified"))
      (node (ref "D1") (pin "1") (pinfunction "K_1") (pintype "unspecified"))
      (node (ref "D10") (pin "1") (pinfunction "K_1") (pintype "unspecified"))
      (node (ref "D11") (pin "1") (pinfunction "K_1") (pintype "unspecified"))
      (node (ref "D12") (pin "1") (pinfunction "K_1") (pintype "unspecified"))
      (node (ref "D13") (pin "1") (pinfunction "K_1") (pintype "unspecified"))
      (node (ref "D14") (pin "1") (pinfunction "K_1") (pintype "unspecified"))
      (node (ref "D15") (pin "1") (pinfunction "K_1") (pintype "unspecified"))
      (node (ref "D2") (pin "1") (pinfunction "K_1") (pintype "unspecified"))
      (node (ref "D3") (pin "1") (pinfunction "K_1") (pintype "unspecified"))
      (node (ref "D4") (pin "1") (pinfunction "K_1") (pintype "unspecified"))
      (node (ref "D5") (pin "1") (pinfunction "K_1") (pintype "unspecified"))
      (node (ref "D6") (pin "1") (pinfunction "K_1") (pintype "unspecified"))
      (node (ref "D7") (pin "1") (pinfunction "K_1") (pintype "unspecified"))
      (node (ref "D8") (pin "1") (pinfunction "K_1") (pintype "unspecified"))
      (node (ref "D9") (pin "1") (pinfunction "K_1") (pintype "unspecified"))
      (node (ref "PCA-A1") (pin "14") (pinfunction "VSS_14") (pintype "unspecified"))
      (node (ref "PCA-A1") (pin "25") (pinfunction "EXTCLK_25") (pintype "unspecified"))
      (node (ref "PCA-B1") (pin "14") (pinfunction "VSS_14") (pintype "unspecified"))
      (node (ref "PCA-B1") (pin "25") (pinfunction "EXTCLK_25") (pintype "unspecified"))
      (node (ref "PCA-C1") (pin "14") (pinfunction "VSS_14") (pintype "unspecified"))
      (node (ref "PCA-C1") (pin "25") (pinfunction "EXTCLK_25") (pintype "unspecified"))
      (node (ref "PCA-D1") (pin "14") (pinfunction "VSS_14") (pintype "unspecified"))
      (node (ref "PCA-D1") (pin "25") (pinfunction "EXTCLK_25") (pintype "unspecified"))
      (node (ref "R11") (pin "2") (pinfunction "2_2") (pintype "input"))
      (node (ref "R12") (pin "1") (pinfunction "1_1") (pintype "input"))
      (node (ref "R13") (pin "1") (pinfunction "1_1") (pintype "input"))
      (node (ref "R14") (pin "1") (pinfunction "1_1") (pintype "input"))
      (node (ref "R15") (pin "1") (pinfunction "1_1") (pintype "input"))
      (node (ref "R16") (pin "1") (pinfunction "1_1") (pintype "input"))
      (node (ref "R17") (pin "2") (pinfunction "2_2") (pintype "input"))
      (node (ref "R18") (pin "2") (pinfunction "2_2") (pintype "input"))
      (node (ref "R19") (pin "1") (pinfunction "1_1") (pintype "input"))
      (node (ref "R2") (pin "1") (pinfunction "1_1") (pintype "input"))
      (node (ref "R20") (pin "1") (pinfunction "1_1") (pintype "input"))
      (node (ref "R21") (pin "1") (pinfunction "1_1") (pintype "input"))
      (node (ref "R22") (pin "1") (pinfunction "1_1") (pintype "input"))
      (node (ref "R25") (pin "1") (pinfunction "1_1") (pintype "input"))
      (node (ref "R26") (pin "1") (pinfunction "1_1") (pintype "input"))
      (node (ref "R27") (pin "1") (pinfunction "1_1") (pintype "input"))
      (node (ref "R28") (pin "2") (pinfunction "2_2") (pintype "input"))
      (node (ref "R29") (pin "2") (pinfunction "2_2") (pintype "input"))
      (node (ref "R3") (pin "2") (pinfunction "2_2") (pintype "input"))
      (node (ref "R30") (pin "2") (pinfunction "2_2") (pintype "input"))
      (node (ref "R35") (pin "2") (pinfunction "2_2") (pintype "input"))
      (node (ref "R36") (pin "2") (pinfunction "2_2") (pintype "input"))
      (node (ref "R4") (pin "2") (pinfunction "2_2") (pintype "input"))
      (node (ref "R40") (pin "2") (pinfunction "2_2") (pintype "input"))
      (node (ref "R41") (pin "2") (pinfunction "2_2") (pintype "input"))
      (node (ref "R6") (pin "1") (pinfunction "1_1") (pintype "input"))
      (node (ref "R7") (pin "1") (pinfunction "1_1") (pintype "input"))
      (node (ref "R8") (pin "1") (pinfunction "1_1") (pintype "input"))
      (node (ref "R9") (pin "2") (pinfunction "2_2") (pintype "input"))
      (node (ref "TVS1") (pin "2") (pinfunction "GND_2") (pintype "unspecified"))
      (node (ref "U4") (pin "2") (pinfunction "GND_2") (pintype "unspecified"))
      (node (ref "U5") (pin "47") (pinfunction "VREG_PGND_47") (pintype "unspecified"))
      (node (ref "U5") (pin "61") (pinfunction "EP_61") (pintype "unspecified"))
      (node (ref "USB1") (pin "0") (pinfunction "0_0") (pintype "unspecified"))
      (node (ref "USB1") (pin "1") (pinfunction "B12_1") (pintype "unspecified"))
      (node (ref "USB1") (pin "6") (pinfunction "A12_6") (pintype "unspecified"))
      (node (ref "USB3") (pin "1") (pinfunction "SHELL_1") (pintype "unspecified"))
      (node (ref "USB3") (pin "2") (pinfunction "SHELL_2") (pintype "unspecified"))
      (node (ref "USB3") (pin "3") (pinfunction "SHELL_3") (pintype "unspecified"))
      (node (ref "USB3") (pin "4") (pinfunction "SHELL_4") (pintype "unspecified"))
      (node (ref "USB3") (pin "A1B12") (pinfunction "GND_A1B12") (pintype "unspecified"))
      (node (ref "USB3") (pin "B1A12") (pinfunction "GND_B1A12") (pintype "unspecified"))
      (node (ref "X1") (pin "2") (pinfunction "GND_2") (pintype "input"))
      (node (ref "X1") (pin "4") (pinfunction "GND_4") (pintype "input"))
    )
    (net (code "8") (name "GPIO1") (class "Default")
      (node (ref "U5") (pin "3") (pinfunction "GPIO1_3") (pintype "unspecified"))
    )
    (net (code "9") (name "LDR_ADC") (class "Default")
      (node (ref "C47") (pin "1") (pinfunction "1_1") (pintype "input"))
      (node (ref "LDR1") (pin "2") (pinfunction "E_2") (pintype "input"))
      (node (ref "R3") (pin "1") (pinfunction "1_1") (pintype "input"))
      (node (ref "U5") (pin "41") (pinfunction "GPIO27_ADC1_41") (pintype "unspecified"))
    )
    (net (code "10") (name "Net-(A0-A)") (class "Default")
      (node (ref "A0") (pin "2") (pinfunction "A_2") (pintype "unspecified"))
      (node (ref "PCA-A1") (pin "6") (pinfunction "LED0_6") (pintype "unspecified"))
    )
    (net (code "11") (name "Net-(A1-A)") (class "Default")
      (node (ref "A1") (pin "2") (pinfunction "A_2") (pintype "unspecified"))
      (node (ref "PCA-A1") (pin "7") (pinfunction "LED1_7") (pintype "unspecified"))
    )
    (net (code "12") (name "Net-(A2-A)") (class "Default")
      (node (ref "A2") (pin "2") (pinfunction "A_2") (pintype "unspecified"))
      (node (ref "PCA-A1") (pin "8") (pinfunction "LED2_8") (pintype "unspecified"))
    )
    (net (code "13") (name "Net-(A3-A)") (class "Default")
      (node (ref "A3") (pin "2") (pinfunction "A_2") (pintype "unspecified"))
      (node (ref "PCA-A1") (pin "9") (pinfunction "LED3_9") (pintype "unspecified"))
    )
    (net (code "14") (name "Net-(A4-A)") (class "Default")
      (node (ref "A4") (pin "2") (pinfunction "A_2") (pintype "unspecified"))
      (node (ref "PCA-A1") (pin "10") (pinfunction "LED4_10") (pintype "unspecified"))
    )
    (net (code "15") (name "Net-(A5-A)") (class "Default")
      (node (ref "A5") (pin "2") (pinfunction "A_2") (pintype "unspecified"))
      (node (ref "PCA-A1") (pin "11") (pinfunction "LED5_11") (pintype "unspecified"))
    )
    (net (code "16") (name "Net-(A6-A)") (class "Default")
      (node (ref "A6") (pin "2") (pinfunction "A_2") (pintype "unspecified"))
      (node (ref "PCA-A1") (pin "12") (pinfunction "LED6_12") (pintype "unspecified"))
    )
    (net (code "17") (name "Net-(A7-A)") (class "Default")
      (node (ref "A7") (pin "2") (pinfunction "A_2") (pintype "unspecified"))
      (node (ref "PCA-A1") (pin "13") (pinfunction "LED7_13") (pintype "unspecified"))
    )
    (net (code "18") (name "Net-(A8-A)") (class "Default")
      (node (ref "A8") (pin "2") (pinfunction "A_2") (pintype "unspecified"))
      (node (ref "PCA-A1") (pin "15") (pinfunction "LED8_15") (pintype "unspecified"))
    )
    (net (code "19") (name "Net-(A9-A)") (class "Default")
      (node (ref "A9") (pin "2") (pinfunction "A_2") (pintype "unspecified"))
      (node (ref "PCA-A1") (pin "16") (pinfunction "LED9_16") (pintype "unspecified"))
    )
    (net (code "20") (name "Net-(A10-A)") (class "Default")
      (node (ref "A10") (pin "2") (pinfunction "A_2") (pintype "unspecified"))
      (node (ref "PCA-A1") (pin "17") (pinfunction "LED10_17") (pintype "unspecified"))
    )
    (net (code "21") (name "Net-(A11-A)") (class "Default")
      (node (ref "A11") (pin "2") (pinfunction "A_2") (pintype "unspecified"))
      (node (ref "PCA-A1") (pin "18") (pinfunction "LED11_18") (pintype "unspecified"))
    )
    (net (code "22") (name "Net-(A12-A)") (class "Default")
      (node (ref "A12") (pin "2") (pinfunction "A_2") (pintype "unspecified"))
      (node (ref "PCA-A1") (pin "19") (pinfunction "LED12_19") (pintype "unspecified"))
    )
    (net (code "23") (name "Net-(A13-A)") (class "Default")
      (node (ref "A13") (pin "2") (pinfunction "A_2") (pintype "unspecified"))
      (node (ref "PCA-A1") (pin "20") (pinfunction "LED13_20") (pintype "unspecified"))
    )
    (net (code "24") (name "Net-(A14-A)") (class "Default")
      (node (ref "A14") (pin "2") (pinfunction "A_2") (pintype "unspecified"))
      (node (ref "PCA-A1") (pin "21") (pinfunction "LED14_21") (pintype "unspecified"))
    )
    (net (code "25") (name "Net-(A15-A)") (class "Default")
      (node (ref "A15") (pin "2") (pinfunction "A_2") (pintype "unspecified"))
      (node (ref "PCA-A1") (pin "22") (pinfunction "LED15_22") (pintype "unspecified"))
    )
    (net (code "26") (name "Net-(B0-A)") (class "Default")
      (node (ref "B0") (pin "2") (pinfunction "A_2") (pintype "unspecified"))
      (node (ref "PCA-B1") (pin "6") (pinfunction "LED0_6") (pintype "unspecified"))
    )
    (net (code "27") (name "Net-(B1-A)") (class "Default")
      (node (ref "B1") (pin "2") (pinfunction "A_2") (pintype "unspecified"))
      (node (ref "PCA-B1") (pin "7") (pinfunction "LED1_7") (pintype "unspecified"))
    )
    (net (code "28") (name "Net-(B2-A)") (class "Default")
      (node (ref "B2") (pin "2") (pinfunction "A_2") (pintype "unspecified"))
      (node (ref "PCA-B1") (pin "8") (pinfunction "LED2_8") (pintype "unspecified"))
    )
    (net (code "29") (name "Net-(B3-A)") (class "Default")
      (node (ref "B3") (pin "2") (pinfunction "A_2") (pintype "unspecified"))
      (node (ref "PCA-B1") (pin "9") (pinfunction "LED3_9") (pintype "unspecified"))
    )
    (net (code "30") (name "Net-(B4-A)") (class "Default")
      (node (ref "B4") (pin "2") (pinfunction "A_2") (pintype "unspecified"))
      (node (ref "PCA-B1") (pin "10") (pinfunction "LED4_10") (pintype "unspecified"))
    )
    (net (code "31") (name "Net-(B5-A)") (class "Default")
      (node (ref "B5") (pin "2") (pinfunction "A_2") (pintype "unspecified"))
      (node (ref "PCA-B1") (pin "11") (pinfunction "LED5_11") (pintype "unspecified"))
    )
    (net (code "32") (name "Net-(B6-A)") (class "Default")
      (node (ref "B6") (pin "2") (pinfunction "A_2") (pintype "unspecified"))
      (node (ref "PCA-B1") (pin "12") (pinfunction "LED6_12") (pintype "unspecified"))
    )
    (net (code "33") (name "Net-(B7-A)") (class "Default")
      (node (ref "B7") (pin "2") (pinfunction "A_2") (pintype "unspecified"))
      (node (ref "PCA-B1") (pin "13") (pinfunction "LED7_13") (pintype "unspecified"))
    )
    (net (code "34") (name "Net-(B8-A)") (class "Default")
      (node (ref "B8") (pin "2") (pinfunction "A_2") (pintype "unspecified"))
      (node (ref "PCA-B1") (pin "15") (pinfunction "LED8_15") (pintype "unspecified"))
    )
    (net (code "35") (name "Net-(B9-A)") (class "Default")
      (node (ref "B9") (pin "2") (pinfunction "A_2") (pintype "unspecified"))
      (node (ref "PCA-B1") (pin "16") (pinfunction "LED9_16") (pintype "unspecified"))
    )
    (net (code "36") (name "Net-(B10-A)") (class "Default")
      (node (ref "B10") (pin "2") (pinfunction "A_2") (pintype "unspecified"))
      (node (ref "PCA-B1") (pin "17") (pinfunction "LED10_17") (pintype "unspecified"))
    )
    (net (code "37") (name "Net-(B11-A)") (class "Default")
      (node (ref "B11") (pin "2") (pinfunction "A_2") (pintype "unspecified"))
      (node (ref "PCA-B1") (pin "18") (pinfunction "LED11_18") (pintype "unspecified"))
    )
    (net (code "38") (name "Net-(B12-A)") (class "Default")
      (node (ref "B12") (pin "2") (pinfunction "A_2") (pintype "unspecified"))
      (node (ref "PCA-B1") (pin "19") (pinfunction "LED12_19") (pintype "unspecified"))
    )
    (net (code "39") (name "Net-(B13-A)") (class "Default")
      (node (ref "B13") (pin "2") (pinfunction "A_2") (pintype "unspecified"))
      (node (ref "PCA-B1") (pin "20") (pinfunction "LED13_20") (pintype "unspecified"))
    )
    (net (code "40") (name "Net-(B14-A)") (class "Default")
      (node (ref "B14") (pin "2") (pinfunction "A_2") (pintype "unspecified"))
      (node (ref "PCA-B1") (pin "21") (pinfunction "LED14_21") (pintype "unspecified"))
    )
    (net (code "41") (name "Net-(B15-A)") (class "Default")
      (node (ref "B15") (pin "2") (pinfunction "A_2") (pintype "unspecified"))
      (node (ref "PCA-B1") (pin "22") (pinfunction "LED15_22") (pintype "unspecified"))
    )
    (net (code "42") (name "Net-(C0-A)") (class "Default")
      (node (ref "C0") (pin "2") (pinfunction "A_2") (pintype "unspecified"))
      (node (ref "PCA-C1") (pin "6") (pinfunction "LED0_6") (pintype "unspecified"))
    )
    (net (code "43") (name "Net-(C1-A)") (class "Default")
      (node (ref "C1") (pin "2") (pinfunction "A_2") (pintype "unspecified"))
      (node (ref "PCA-C1") (pin "7") (pinfunction "LED1_7") (pintype "unspecified"))
    )
    (net (code "44") (name "Net-(C2-A)") (class "Default")
      (node (ref "C2") (pin "2") (pinfunction "A_2") (pintype "unspecified"))
      (node (ref "PCA-C1") (pin "8") (pinfunction "LED2_8") (pintype "unspecified"))
    )
    (net (code "45") (name "Net-(C3-A)") (class "Default")
      (node (ref "C3") (pin "2") (pinfunction "A_2") (pintype "unspecified"))
      (node (ref "PCA-C1") (pin "9") (pinfunction "LED3_9") (pintype "unspecified"))
    )
    (net (code "46") (name "Net-(C4-A)") (class "Default")
      (node (ref "C4") (pin "2") (pinfunction "A_2") (pintype "unspecified"))
      (node (ref "PCA-C1") (pin "10") (pinfunction "LED4_10") (pintype "unspecified"))
    )
    (net (code "47") (name "Net-(C5-A)") (class "Default")
      (node (ref "C5") (pin "2") (pinfunction "A_2") (pintype "unspecified"))
      (node (ref "PCA-C1") (pin "11") (pinfunction "LED5_11") (pintype "unspecified"))
    )
    (net (code "48") (name "Net-(C6-A)") (class "Default")
      (node (ref "C6") (pin "2") (pinfunction "A_2") (pintype "unspecified"))
      (node (ref "PCA-C1") (pin "12") (pinfunction "LED6_12") (pintype "unspecified"))
    )
    (net (code "49") (name "Net-(C7-A)") (class "Default")
      (node (ref "C7") (pin "2") (pinfunction "A_2") (pintype "unspecified"))
      (node (ref "PCA-C1") (pin "13") (pinfunction "LED7_13") (pintype "unspecified"))
    )
    (net (code "50") (name "Net-(C8-A)") (class "Default")
      (node (ref "C8") (pin "2") (pinfunction "A_2") (pintype "unspecified"))
      (node (ref "PCA-C1") (pin "15") (pinfunction "LED8_15") (pintype "unspecified"))
    )
    (net (code "51") (name "Net-(C9-A)") (class "Default")
      (node (ref "C9") (pin "2") (pinfunction "A_2") (pintype "unspecified"))
      (node (ref "PCA-C1") (pin "16") (pinfunction "LED9_16") (pintype "unspecified"))
    )
    (net (code "52") (name "Net-(C10-A)") (class "Default")
      (node (ref "C10") (pin "2") (pinfunction "A_2") (pintype "unspecified"))
      (node (ref "PCA-C1") (pin "17") (pinfunction "LED10_17") (pintype "unspecified"))
    )
    (net (code "53") (name "Net-(C11-A)") (class "Default")
      (node (ref "C11") (pin "2") (pinfunction "A_2") (pintype "unspecified"))
      (node (ref "PCA-C1") (pin "18") (pinfunction "LED11_18") (pintype "unspecified"))
    )
    (net (code "54") (name "Net-(C12-A)") (class "Default")
      (node (ref "C12") (pin "2") (pinfunction "A_2") (pintype "unspecified"))
      (node (ref "PCA-C1") (pin "19") (pinfunction "LED12_19") (pintype "unspecified"))
    )
    (net (code "55") (name "Net-(C13-A)") (class "Default")
      (node (ref "C13") (pin "2") (pinfunction "A_2") (pintype "unspecified"))
      (node (ref "PCA-C1") (pin "20") (pinfunction "LED13_20") (pintype "unspecified"))
    )
    (net (code "56") (name "Net-(C14-A)") (class "Default")
      (node (ref "C14") (pin "2") (pinfunction "A_2") (pintype "unspecified"))
      (node (ref "PCA-C1") (pin "21") (pinfunction "LED14_21") (pintype "unspecified"))
    )
    (net (code "57") (name "Net-(C15-A)") (class "Default")
      (node (ref "C15") (pin "2") (pinfunction "A_2") (pintype "unspecified"))
      (node (ref "PCA-C1") (pin "22") (pinfunction "LED15_22") (pintype "unspecified"))
    )
    (net (code "58") (name "Net-(C33-Pad1)") (class "Default")
      (node (ref "C33") (pin "1") (pinfunction "1_1") (pintype "input"))
      (node (ref "R45") (pin "1") (pinfunction "1_1") (pintype "input"))
      (node (ref "X1") (pin "3") (pinfunction "3_3") (pintype "input"))
    )
    (net (code "59") (name "Net-(D0-A)") (class "Default")
      (node (ref "D0") (pin "2") (pinfunction "A_2") (pintype "unspecified"))
      (node (ref "PCA-D1") (pin "6") (pinfunction "LED0_6") (pintype "unspecified"))
    )
    (net (code "60") (name "Net-(D1-A)") (class "Default")
      (node (ref "D1") (pin "2") (pinfunction "A_2") (pintype "unspecified"))
      (node (ref "PCA-D1") (pin "7") (pinfunction "LED1_7") (pintype "unspecified"))
    )
    (net (code "61") (name "Net-(D2-A)") (class "Default")
      (node (ref "D2") (pin "2") (pinfunction "A_2") (pintype "unspecified"))
      (node (ref "PCA-D1") (pin "8") (pinfunction "LED2_8") (pintype "unspecified"))
    )
    (net (code "62") (name "Net-(D3-A)") (class "Default")
      (node (ref "D3") (pin "2") (pinfunction "A_2") (pintype "unspecified"))
      (node (ref "PCA-D1") (pin "9") (pinfunction "LED3_9") (pintype "unspecified"))
    )
    (net (code "63") (name "Net-(D4-A)") (class "Default")
      (node (ref "D4") (pin "2") (pinfunction "A_2") (pintype "unspecified"))
      (node (ref "PCA-D1") (pin "10") (pinfunction "LED4_10") (pintype "unspecified"))
    )
    (net (code "64") (name "Net-(D5-A)") (class "Default")
      (node (ref "D5") (pin "2") (pinfunction "A_2") (pintype "unspecified"))
      (node (ref "PCA-D1") (pin "11") (pinfunction "LED5_11") (pintype "unspecified"))
    )
    (net (code "65") (name "Net-(D6-A)") (class "Default")
      (node (ref "D6") (pin "2") (pinfunction "A_2") (pintype "unspecified"))
      (node (ref "PCA-D1") (pin "12") (pinfunction "LED6_12") (pintype "unspecified"))
    )
    (net (code "66") (name "Net-(D7-A)") (class "Default")
      (node (ref "D7") (pin "2") (pinfunction "A_2") (pintype "unspecified"))
      (node (ref "PCA-D1") (pin "13") (pinfunction "LED7_13") (pintype "unspecified"))
    )
    (net (code "67") (name "Net-(D8-A)") (class "Default")
      (node (ref "D8") (pin "2") (pinfunction "A_2") (pintype "unspecified"))
      (node (ref "PCA-D1") (pin "15") (pinfunction "LED8_15") (pintype "unspecified"))
    )
    (net (code "68") (name "Net-(D9-A)") (class "Default")
      (node (ref "D9") (pin "2") (pinfunction "A_2") (pintype "unspecified"))
      (node (ref "PCA-D1") (pin "16") (pinfunction "LED9_16") (pintype "unspecified"))
    )
    (net (code "69") (name "Net-(D10-A)") (class "Default")
      (node (ref "D10") (pin "2") (pinfunction "A_2") (pintype "unspecified"))
      (node (ref "PCA-D1") (pin "17") (pinfunction "LED10_17") (pintype "unspecified"))
    )
    (net (code "70") (name "Net-(D11-A)") (class "Default")
      (node (ref "D11") (pin "2") (pinfunction "A_2") (pintype "unspecified"))
      (node (ref "PCA-D1") (pin "18") (pinfunction "LED11_18") (pintype "unspecified"))
    )
    (net (code "71") (name "Net-(D12-A)") (class "Default")
      (node (ref "D12") (pin "2") (pinfunction "A_2") (pintype "unspecified"))
      (node (ref "PCA-D1") (pin "19") (pinfunction "LED12_19") (pintype "unspecified"))
    )
    (net (code "72") (name "Net-(D13-A)") (class "Default")
      (node (ref "D13") (pin "2") (pinfunction "A_2") (pintype "unspecified"))
      (node (ref "PCA-D1") (pin "20") (pinfunction "LED13_20") (pintype "unspecified"))
    )
    (net (code "73") (name "Net-(D14-A)") (class "Default")
      (node (ref "D14") (pin "2") (pinfunction "A_2") (pintype "unspecified"))
      (node (ref "PCA-D1") (pin "21") (pinfunction "LED14_21") (pintype "unspecified"))
    )
    (net (code "74") (name "Net-(D15-A)") (class "Default")
      (node (ref "D15") (pin "2") (pinfunction "A_2") (pintype "unspecified"))
      (node (ref "PCA-D1") (pin "22") (pinfunction "LED15_22") (pintype "unspecified"))
    )
    (net (code "75") (name "Net-(PCA-A1-A0)") (class "Default")
      (node (ref "PCA-A1") (pin "1") (pinfunction "A0_1") (pintype "unspecified"))
      (node (ref "R12") (pin "2") (pinfunction "2_2") (pintype "input"))
    )
    (net (code "76") (name "Net-(PCA-A1-A1)") (class "Default")
      (node (ref "PCA-A1") (pin "2") (pinfunction "A1_2") (pintype "unspecified"))
      (node (ref "R13") (pin "2") (pinfunction "2_2") (pintype "input"))
    )
    (net (code "77") (name "Net-(PCA-A1-A2)") (class "Default")
      (node (ref "PCA-A1") (pin "3") (pinfunction "A2_3") (pintype "unspecified"))
      (node (ref "R14") (pin "2") (pinfunction "2_2") (pintype "input"))
    )
    (net (code "78") (name "Net-(PCA-A1-A3)") (class "Default")
      (node (ref "PCA-A1") (pin "4") (pinfunction "A3_4") (pintype "unspecified"))
      (node (ref "R15") (pin "2") (pinfunction "2_2") (pintype "input"))
    )
    (net (code "79") (name "Net-(PCA-A1-A4)") (class "Default")
      (node (ref "PCA-A1") (pin "5") (pinfunction "A4_5") (pintype "unspecified"))
      (node (ref "R16") (pin "2") (pinfunction "2_2") (pintype "input"))
    )
    (net (code "80") (name "Net-(PCA-A1-A5)") (class "Default")
      (node (ref "PCA-A1") (pin "24") (pinfunction "A5_24") (pintype "unspecified"))
      (node (ref "R11") (pin "1") (pinfunction "1_1") (pintype "input"))
    )
    (net (code "81") (name "Net-(PCA-A1-OE#)") (class "Default")
      (node (ref "PCA-A1") (pin "23") (pinfunction "OE#_23") (pintype "unspecified"))
      (node (ref "R28") (pin "1") (pinfunction "1_1") (pintype "input"))
    )
    (net (code "82") (name "Net-(PCA-B1-A1)") (class "Default")
      (node (ref "PCA-B1") (pin "2") (pinfunction "A1_2") (pintype "unspecified"))
      (node (ref "R2") (pin "2") (pinfunction "2_2") (pintype "input"))
    )
    (net (code "83") (name "Net-(PCA-B1-A2)") (class "Default")
      (node (ref "PCA-B1") (pin "3") (pinfunction "A2_3") (pintype "unspecified"))
      (node (ref "R6") (pin "2") (pinfunction "2_2") (pintype "input"))
    )
    (net (code "84") (name "Net-(PCA-B1-A3)") (class "Default")
      (node (ref "PCA-B1") (pin "4") (pinfunction "A3_4") (pintype "unspecified"))
      (node (ref "R7") (pin "2") (pinfunction "2_2") (pintype "input"))
    )
    (net (code "85") (name "Net-(PCA-B1-A4)") (class "Default")
      (node (ref "PCA-B1") (pin "5") (pinfunction "A4_5") (pintype "unspecified"))
      (node (ref "R8") (pin "2") (pinfunction "2_2") (pintype "input"))
    )
    (net (code "86") (name "Net-(PCA-B1-A5)") (class "Default")
      (node (ref "PCA-B1") (pin "24") (pinfunction "A5_24") (pintype "unspecified"))
      (node (ref "R4") (pin "1") (pinfunction "1_1") (pintype "input"))
    )
    (net (code "87") (name "Net-(PCA-B1-OE#)") (class "Default")
      (node (ref "PCA-B1") (pin "23") (pinfunction "OE#_23") (pintype "unspecified"))
      (node (ref "R9") (pin "1") (pinfunction "1_1") (pintype "input"))
    )
    (net (code "88") (name "Net-(PCA-C1-A0)") (class "Default")
      (node (ref "PCA-C1") (pin "1") (pinfunction "A0_1") (pintype "unspecified"))
      (node (ref "R19") (pin "2") (pinfunction "2_2") (pintype "input"))
    )
    (net (code "89") (name "Net-(PCA-C1-A2)") (class "Default")
      (node (ref "PCA-C1") (pin "3") (pinfunction "A2_3") (pintype "unspecified"))
      (node (ref "R20") (pin "2") (pinfunction "2_2") (pintype "input"))
    )
    (net (code "90") (name "Net-(PCA-C1-A3)") (class "Default")
      (node (ref "PCA-C1") (pin "4") (pinfunction "A3_4") (pintype "unspecified"))
      (node (ref "R21") (pin "2") (pinfunction "2_2") (pintype "input"))
    )
    (net (code "91") (name "Net-(PCA-C1-A4)") (class "Default")
      (node (ref "PCA-C1") (pin "5") (pinfunction "A4_5") (pintype "unspecified"))
      (node (ref "R22") (pin "2") (pinfunction "2_2") (pintype "input"))
    )
    (net (code "92") (name "Net-(PCA-C1-A5)") (class "Default")
      (node (ref "PCA-C1") (pin "24") (pinfunction "A5_24") (pintype "unspecified"))
      (node (ref "R17") (pin "1") (pinfunction "1_1") (pintype "input"))
    )
    (net (code "93") (name "Net-(PCA-C1-OE#)") (class "Default")
      (node (ref "PCA-C1") (pin "23") (pinfunction "OE#_23") (pintype "unspecified"))
      (node (ref "R18") (pin "1") (pinfunction "1_1") (pintype "input"))
    )
    (net (code "94") (name "Net-(PCA-D1-A2)") (class "Default")
      (node (ref "PCA-D1") (pin "3") (pinfunction "A2_3") (pintype "unspecified"))
      (node (ref "R25") (pin "2") (pinfunction "2_2") (pintype "input"))
    )
    (net (code "95") (name "Net-(PCA-D1-A3)") (class "Default")
      (node (ref "PCA-D1") (pin "4") (pinfunction "A3_4") (pintype "unspecified"))
      (node (ref "R26") (pin "2") (pinfunction "2_2") (pintype "input"))
    )
    (net (code "96") (name "Net-(PCA-D1-A4)") (class "Default")
      (node (ref "PCA-D1") (pin "5") (pinfunction "A4_5") (pintype "unspecified"))
      (node (ref "R27") (pin "2") (pinfunction "2_2") (pintype "input"))
    )
    (net (code "97") (name "Net-(PCA-D1-A5)") (class "Default")
      (node (ref "PCA-D1") (pin "24") (pinfunction "A5_24") (pintype "unspecified"))
      (node (ref "R29") (pin "1") (pinfunction "1_1") (pintype "input"))
    )
    (net (code "98") (name "Net-(PCA-D1-OE#)") (class "Default")
      (node (ref "PCA-D1") (pin "23") (pinfunction "OE#_23") (pintype "unspecified"))
      (node (ref "R30") (pin "1") (pinfunction "1_1") (pintype "input"))
    )
    (net (code "99") (name "Net-(Q1-G)") (class "Default")
      (node (ref "Q1") (pin "1") (pinfunction "G_1") (pintype "unspecified"))
      (node (ref "R31") (pin "1") (pinfunction "1_1") (pintype "input"))
      (node (ref "R32") (pin "1") (pinfunction "1_1") (pintype "input"))
    )
    (net (code "100") (name "Net-(U5-QSPI_SS)") (class "Default")
      (node (ref "R46") (pin "1") (pinfunction "1_1") (pintype "input"))
      (node (ref "U5") (pin "60") (pinfunction "QSPI_SS_60") (pintype "unspecified"))
    )
    (net (code "101") (name "Net-(U5-USB_DM)") (class "Default")
      (node (ref "R43") (pin "2") (pinfunction "2_2") (pintype "input"))
      (node (ref "U5") (pin "51") (pinfunction "USB_DM_51") (pintype "unspecified"))
    )
    (net (code "102") (name "Net-(U5-USB_DP)") (class "Default")
      (node (ref "R44") (pin "2") (pinfunction "2_2") (pintype "input"))
      (node (ref "U5") (pin "52") (pinfunction "USB_DP_52") (pintype "unspecified"))
    )
    (net (code "103") (name "Net-(U5-VREG_AVDD)") (class "Default")
      (node (ref "C46") (pin "1") (pinfunction "1_1") (pintype "input"))
      (node (ref "R42") (pin "1") (pinfunction "1_1") (pintype "input"))
      (node (ref "U5") (pin "46") (pinfunction "VREG_AVDD_46") (pintype "unspecified"))
    )
    (net (code "104") (name "Net-(U5-VREG_LX)") (class "Default")
      (node (ref "L1") (pin "1") (pinfunction "1_1") (pintype "unspecified"))
      (node (ref "U5") (pin "48") (pinfunction "VREG_LX_48") (pintype "unspecified"))
    )
    (net (code "105") (name "Net-(USB1-A5)") (class "Default")
      (node (ref "R40") (pin "1") (pinfunction "1_1") (pintype "input"))
      (node (ref "USB1") (pin "3") (pinfunction "A5_3") (pintype "unspecified"))
    )
    (net (code "106") (name "Net-(USB1-B5)") (class "Default")
      (node (ref "R41") (pin "1") (pinfunction "1_1") (pintype "input"))
      (node (ref "USB1") (pin "4") (pinfunction "B5_4") (pintype "unspecified"))
    )
    (net (code "107") (name "Net-(USB3-CC1)") (class "Default")
      (node (ref "R35") (pin "1") (pinfunction "1_1") (pintype "input"))
      (node (ref "USB3") (pin "A5") (pinfunction "CC1_A5") (pintype "unspecified"))
    )
    (net (code "108") (name "Net-(USB3-CC2)") (class "Default")
      (node (ref "R36") (pin "1") (pinfunction "1_1") (pintype "input"))
      (node (ref "USB3") (pin "B5") (pinfunction "CC2_B5") (pintype "unspecified"))
    )
    (net (code "109") (name "PWR_SW_CTRL") (class "Default")
      (node (ref "R32") (pin "2") (pinfunction "2_2") (pintype "input"))
      (node (ref "U5") (pin "40") (pinfunction "GPIO26_ADC0_40") (pintype "unspecified"))
    )
    (net (code "110") (name "QSPI_SS") (class "Default")
      (node (ref "R46") (pin "2") (pinfunction "2_2") (pintype "input"))
    )
    (net (code "111") (name "RUN") (class "Default")
      (node (ref "U5") (pin "26") (pinfunction "RUN_26") (pintype "unspecified"))
    )
    (net (code "112") (name "SCL") (class "Default")
      (node (ref "PCA-A1") (pin "26") (pinfunction "SCL_26") (pintype "unspecified"))
      (node (ref "PCA-B1") (pin "26") (pinfunction "SCL_26") (pintype "unspecified"))
      (node (ref "PCA-C1") (pin "26") (pinfunction "SCL_26") (pintype "unspecified"))
      (node (ref "PCA-D1") (pin "26") (pinfunction "SCL_26") (pintype "unspecified"))
      (node (ref "R23") (pin "2") (pinfunction "2_2") (pintype "input"))
      (node (ref "U5") (pin "10") (pinfunction "GPIO7_10") (pintype "unspecified"))
    )
    (net (code "113") (name "SDA") (class "Default")
      (node (ref "PCA-A1") (pin "27") (pinfunction "SDA_27") (pintype "unspecified"))
      (node (ref "PCA-B1") (pin "27") (pinfunction "SDA_27") (pintype "unspecified"))
      (node (ref "PCA-C1") (pin "27") (pinfunction "SDA_27") (pintype "unspecified"))
      (node (ref "PCA-D1") (pin "27") (pinfunction "SDA_27") (pintype "unspecified"))
      (node (ref "R24") (pin "2") (pinfunction "2_2") (pintype "input"))
      (node (ref "U5") (pin "9") (pinfunction "GPIO6_9") (pintype "unspecified"))
    )
    (net (code "114") (name "SWCLK") (class "Default")
      (node (ref "U5") (pin "24") (pinfunction "SWCLK_24") (pintype "unspecified"))
    )
    (net (code "115") (name "SWD") (class "Default")
      (node (ref "U5") (pin "25") (pinfunction "SWDIO_25") (pintype "unspecified"))
    )
    (net (code "116") (name "XIN") (class "Default")
      (node (ref "C24") (pin "2") (pinfunction "2_2") (pintype "input"))
      (node (ref "U5") (pin "21") (pinfunction "XIN_21") (pintype "unspecified"))
      (node (ref "X1") (pin "1") (pinfunction "1_1") (pintype "input"))
    )
    (net (code "117") (name "XOUT") (class "Default")
      (node (ref "R45") (pin "2") (pinfunction "2_2") (pintype "input"))
      (node (ref "U5") (pin "22") (pinfunction "XOUT_22") (pintype "unspecified"))
    )
    (net (code "118") (name "unconnected-(U4-NC-Pad4)") (class "Default")
      (node (ref "U4") (pin "4") (pinfunction "NC_4") (pintype "unspecified+no_connect"))
    )
    (net (code "119") (name "unconnected-(U5-GPIO0-Pad2)") (class "Default")
      (node (ref "U5") (pin "2") (pinfunction "GPIO0_2") (pintype "unspecified+no_connect"))
    )
    (net (code "120") (name "unconnected-(U5-GPIO2-Pad4)") (class "Default")
      (node (ref "U5") (pin "4") (pinfunction "GPIO2_4") (pintype "unspecified+no_connect"))
    )
    (net (code "121") (name "unconnected-(U5-GPIO3-Pad5)") (class "Default")
      (node (ref "U5") (pin "5") (pinfunction "GPIO3_5") (pintype "unspecified+no_connect"))
    )
    (net (code "122") (name "unconnected-(U5-GPIO4-Pad7)") (class "Default")
      (node (ref "U5") (pin "7") (pinfunction "GPIO4_7") (pintype "unspecified+no_connect"))
    )
    (net (code "123") (name "unconnected-(U5-GPIO5-Pad8)") (class "Default")
      (node (ref "U5") (pin "8") (pinfunction "GPIO5_8") (pintype "unspecified+no_connect"))
    )
    (net (code "124") (name "unconnected-(U5-GPIO8-Pad12)") (class "Default")
      (node (ref "U5") (pin "12") (pinfunction "GPIO8_12") (pintype "unspecified+no_connect"))
    )
    (net (code "125") (name "unconnected-(U5-GPIO9-Pad13)") (class "Default")
      (node (ref "U5") (pin "13") (pinfunction "GPIO9_13") (pintype "unspecified+no_connect"))
    )
    (net (code "126") (name "unconnected-(U5-GPIO10-Pad14)") (class "Default")
      (node (ref "U5") (pin "14") (pinfunction "GPIO10_14") (pintype "unspecified+no_connect"))
    )
    (net (code "127") (name "unconnected-(U5-GPIO11-Pad15)") (class "Default")
      (node (ref "U5") (pin "15") (pinfunction "GPIO11_15") (pintype "unspecified+no_connect"))
    )
    (net (code "128") (name "unconnected-(U5-GPIO12-Pad16)") (class "Default")
      (node (ref "U5") (pin "16") (pinfunction "GPIO12_16") (pintype "unspecified+no_connect"))
    )
    (net (code "129") (name "unconnected-(U5-GPIO13-Pad17)") (class "Default")
      (node (ref "U5") (pin "17") (pinfunction "GPIO13_17") (pintype "unspecified+no_connect"))
    )
    (net (code "130") (name "unconnected-(U5-GPIO14-Pad18)") (class "Default")
      (node (ref "U5") (pin "18") (pinfunction "GPIO14_18") (pintype "unspecified+no_connect"))
    )
    (net (code "131") (name "unconnected-(U5-GPIO15-Pad19)") (class "Default")
      (node (ref "U5") (pin "19") (pinfunction "GPIO15_19") (pintype "unspecified+no_connect"))
    )
    (net (code "132") (name "unconnected-(U5-GPIO16-Pad27)") (class "Default")
      (node (ref "U5") (pin "27") (pinfunction "GPIO16_27") (pintype "unspecified+no_connect"))
    )
    (net (code "133") (name "unconnected-(U5-GPIO17-Pad28)") (class "Default")
      (node (ref "U5") (pin "28") (pinfunction "GPIO17_28") (pintype "unspecified+no_connect"))
    )
    (net (code "134") (name "unconnected-(U5-GPIO18-Pad29)") (class "Default")
      (node (ref "U5") (pin "29") (pinfunction "GPIO18_29") (pintype "unspecified+no_connect"))
    )
    (net (code "135") (name "unconnected-(U5-GPIO19-Pad31)") (class "Default")
      (node (ref "U5") (pin "31") (pinfunction "GPIO19_31") (pintype "unspecified+no_connect"))
    )
    (net (code "136") (name "unconnected-(U5-GPIO20-Pad32)") (class "Default")
      (node (ref "U5") (pin "32") (pinfunction "GPIO20_32") (pintype "unspecified+no_connect"))
    )
    (net (code "137") (name "unconnected-(U5-GPIO21-Pad33)") (class "Default")
      (node (ref "U5") (pin "33") (pinfunction "GPIO21_33") (pintype "unspecified+no_connect"))
    )
    (net (code "138") (name "unconnected-(U5-GPIO22-Pad34)") (class "Default")
      (node (ref "U5") (pin "34") (pinfunction "GPIO22_34") (pintype "unspecified+no_connect"))
    )
    (net (code "139") (name "unconnected-(U5-GPIO23-Pad35)") (class "Default")
      (node (ref "U5") (pin "35") (pinfunction "GPIO23_35") (pintype "unspecified+no_connect"))
    )
    (net (code "140") (name "unconnected-(U5-GPIO24-Pad36)") (class "Default")
      (node (ref "U5") (pin "36") (pinfunction "GPIO24_36") (pintype "unspecified+no_connect"))
    )
    (net (code "141") (name "unconnected-(U5-GPIO25-Pad37)") (class "Default")
      (node (ref "U5") (pin "37") (pinfunction "GPIO25_37") (pintype "unspecified+no_connect"))
    )
    (net (code "142") (name "unconnected-(U5-GPIO28_ADC2-Pad42)") (class "Default")
      (node (ref "U5") (pin "42") (pinfunction "GPIO28_ADC2_42") (pintype "unspecified"))
    )
    (net (code "143") (name "unconnected-(U5-GPIO29_ADC3-Pad43)") (class "Default")
      (node (ref "U5") (pin "43") (pinfunction "GPIO29_ADC3_43") (pintype "unspecified"))
    )
    (net (code "144") (name "unconnected-(U5-QSPI_SCLK-Pad56)") (class "Default")
      (node (ref "U5") (pin "56") (pinfunction "QSPI_SCLK_56") (pintype "unspecified+no_connect"))
    )
    (net (code "145") (name "unconnected-(U5-QSPI_SD0-Pad57)") (class "Default")
      (node (ref "U5") (pin "57") (pinfunction "QSPI_SD0_57") (pintype "unspecified+no_connect"))
    )
    (net (code "146") (name "unconnected-(U5-QSPI_SD1-Pad59)") (class "Default")
      (node (ref "U5") (pin "59") (pinfunction "QSPI_SD1_59") (pintype "unspecified+no_connect"))
    )
    (net (code "147") (name "unconnected-(U5-QSPI_SD2-Pad58)") (class "Default")
      (node (ref "U5") (pin "58") (pinfunction "QSPI_SD2_58") (pintype "unspecified+no_connect"))
    )
    (net (code "148") (name "unconnected-(U5-QSPI_SD3-Pad55)") (class "Default")
      (node (ref "U5") (pin "55") (pinfunction "QSPI_SD3_55") (pintype "unspecified+no_connect"))
    )
    (net (code "149") (name "unconnected-(USB3-SBU1-PadA8)") (class "Default")
      (node (ref "USB3") (pin "A8") (pinfunction "SBU1_A8") (pintype "unspecified+no_connect"))
    )
    (net (code "150") (name "unconnected-(USB3-SBU2-PadB8)") (class "Default")
      (node (ref "USB3") (pin "B8") (pinfunction "SBU2_B8") (pintype "unspecified+no_connect"))
    )
  )
)
